# EIB-128.net
KiCad netlist of a schematic drawn in EAGLE
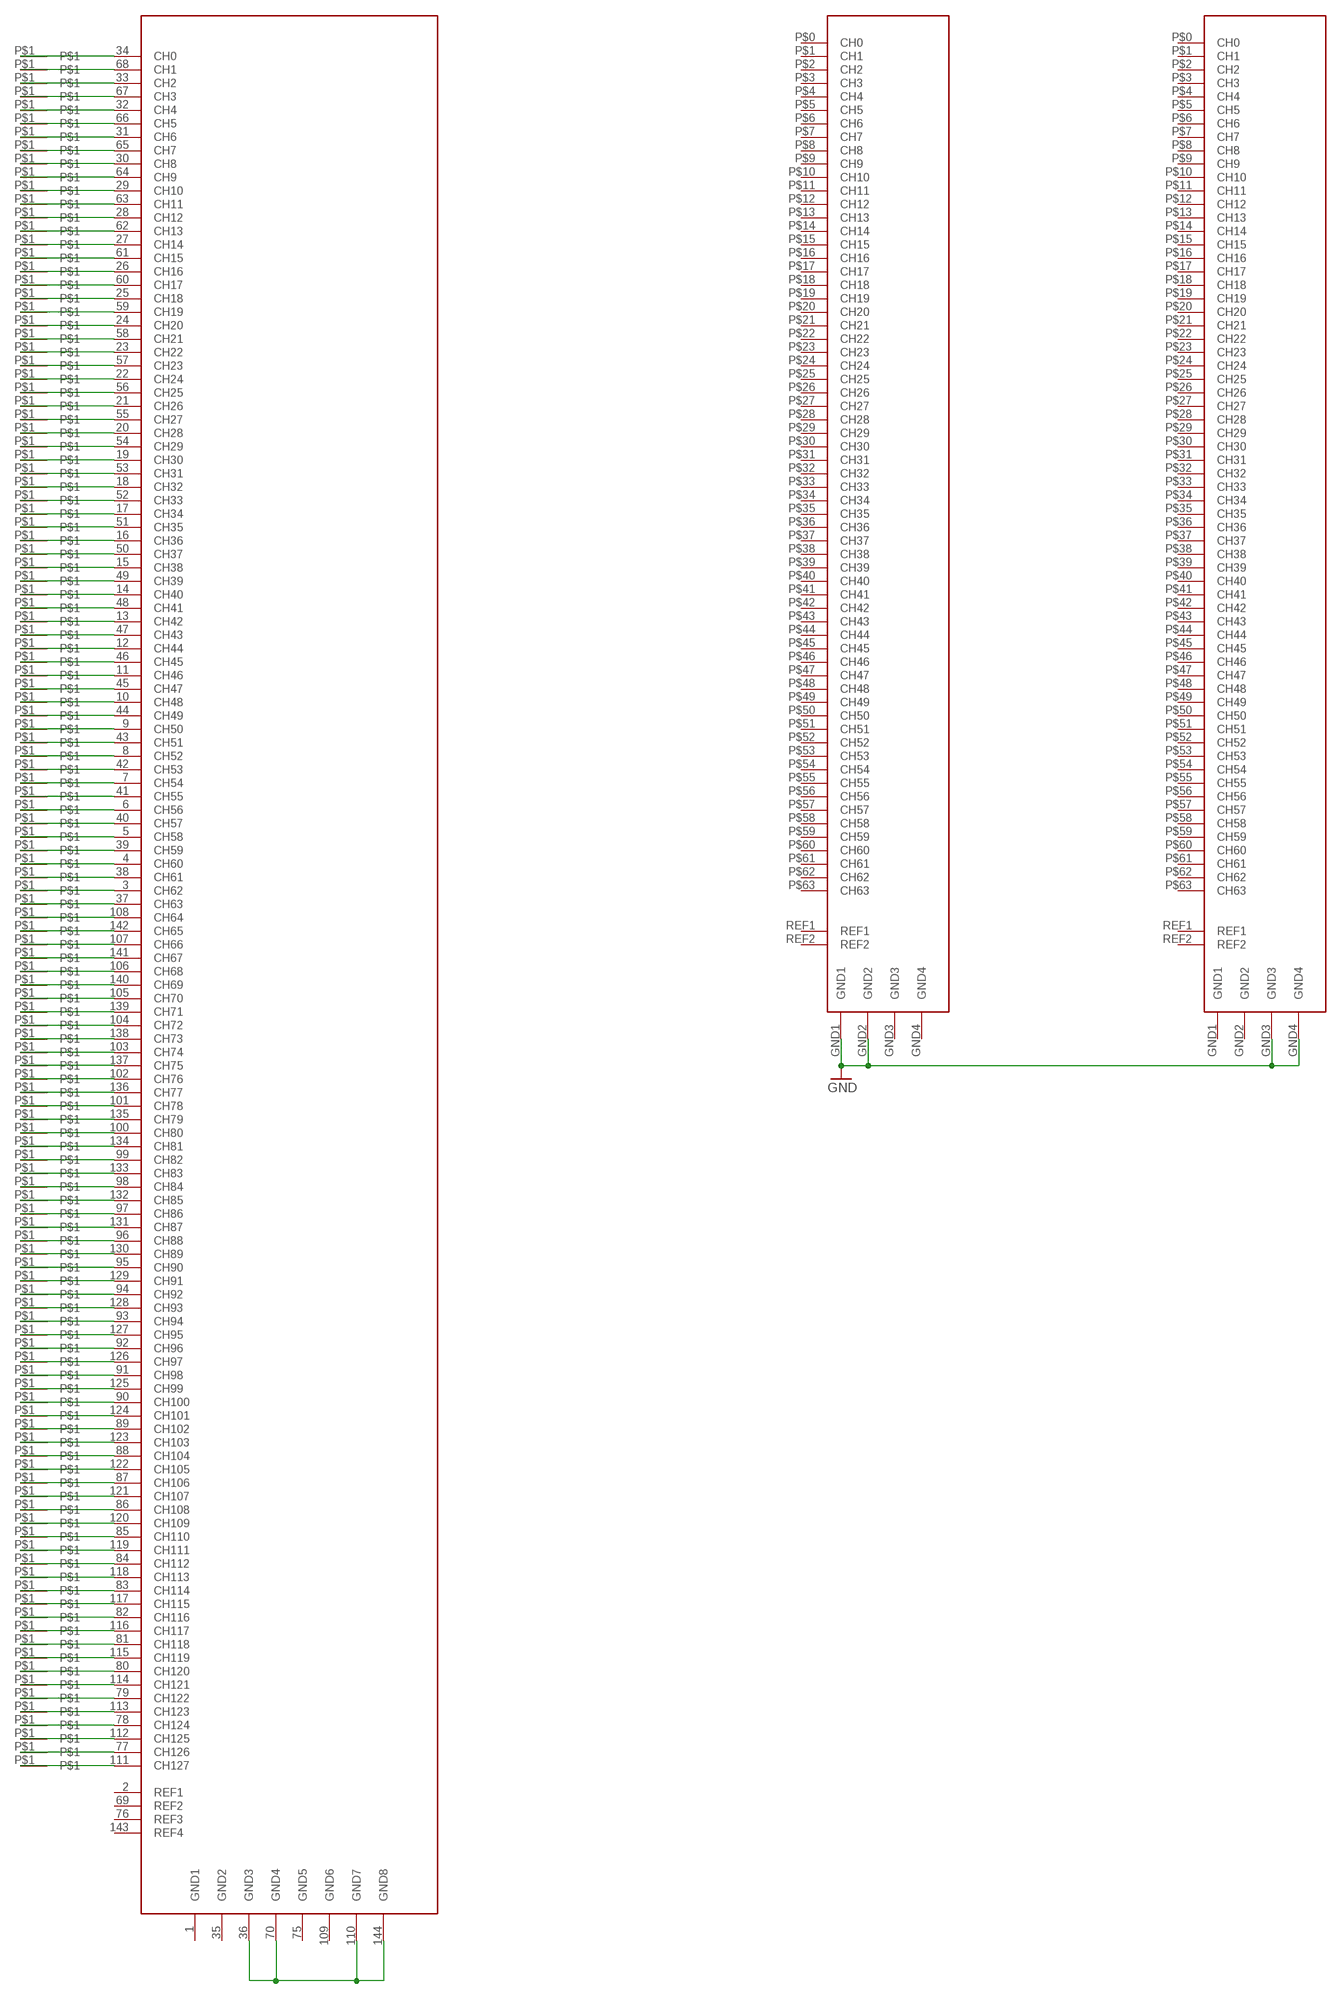
[diagram p0: schematic, sheet 1]

(export (version "E")
  (design (tool "Eeschema 10.0.6"))
  (components
    (comp (ref "H$0")
      (value "TARRAYSHUTTLEHOLE")
      (footprint "eagle-import:TARRAYSHUTTLEHOLE")
      (libsource (lib "eagle-import") (part "TARRAYSHUTTLEHOLE"))
    )
    (comp (ref "H$1")
      (value "TARRAYSHUTTLEHOLE")
      (footprint "eagle-import:TARRAYSHUTTLEHOLE")
      (libsource (lib "eagle-import") (part "TARRAYSHUTTLEHOLE"))
    )
    (comp (ref "H$2")
      (value "TARRAYSHUTTLEHOLE")
      (footprint "eagle-import:TARRAYSHUTTLEHOLE")
      (libsource (lib "eagle-import") (part "TARRAYSHUTTLEHOLE"))
    )
    (comp (ref "H$3")
      (value "TARRAYSHUTTLEHOLE")
      (footprint "eagle-import:TARRAYSHUTTLEHOLE")
      (libsource (lib "eagle-import") (part "TARRAYSHUTTLEHOLE"))
    )
    (comp (ref "H$4")
      (value "TARRAYSHUTTLEHOLE")
      (footprint "eagle-import:TARRAYSHUTTLEHOLE")
      (libsource (lib "eagle-import") (part "TARRAYSHUTTLEHOLE"))
    )
    (comp (ref "H$5")
      (value "TARRAYSHUTTLEHOLE")
      (footprint "eagle-import:TARRAYSHUTTLEHOLE")
      (libsource (lib "eagle-import") (part "TARRAYSHUTTLEHOLE"))
    )
    (comp (ref "H$6")
      (value "TARRAYSHUTTLEHOLE")
      (footprint "eagle-import:TARRAYSHUTTLEHOLE")
      (libsource (lib "eagle-import") (part "TARRAYSHUTTLEHOLE"))
    )
    (comp (ref "H$7")
      (value "TARRAYSHUTTLEHOLE")
      (footprint "eagle-import:TARRAYSHUTTLEHOLE")
      (libsource (lib "eagle-import") (part "TARRAYSHUTTLEHOLE"))
    )
    (comp (ref "H$8")
      (value "TARRAYSHUTTLEHOLE")
      (footprint "eagle-import:TARRAYSHUTTLEHOLE")
      (libsource (lib "eagle-import") (part "TARRAYSHUTTLEHOLE"))
    )
    (comp (ref "H$9")
      (value "TARRAYSHUTTLEHOLE")
      (footprint "eagle-import:TARRAYSHUTTLEHOLE")
      (libsource (lib "eagle-import") (part "TARRAYSHUTTLEHOLE"))
    )
    (comp (ref "H$10")
      (value "TARRAYSHUTTLEHOLE")
      (footprint "eagle-import:TARRAYSHUTTLEHOLE")
      (libsource (lib "eagle-import") (part "TARRAYSHUTTLEHOLE"))
    )
    (comp (ref "H$11")
      (value "TARRAYSHUTTLEHOLE")
      (footprint "eagle-import:TARRAYSHUTTLEHOLE")
      (libsource (lib "eagle-import") (part "TARRAYSHUTTLEHOLE"))
    )
    (comp (ref "H$12")
      (value "TARRAYSHUTTLEHOLE")
      (footprint "eagle-import:TARRAYSHUTTLEHOLE")
      (libsource (lib "eagle-import") (part "TARRAYSHUTTLEHOLE"))
    )
    (comp (ref "H$13")
      (value "TARRAYSHUTTLEHOLE")
      (footprint "eagle-import:TARRAYSHUTTLEHOLE")
      (libsource (lib "eagle-import") (part "TARRAYSHUTTLEHOLE"))
    )
    (comp (ref "H$14")
      (value "TARRAYSHUTTLEHOLE")
      (footprint "eagle-import:TARRAYSHUTTLEHOLE")
      (libsource (lib "eagle-import") (part "TARRAYSHUTTLEHOLE"))
    )
    (comp (ref "H$15")
      (value "TARRAYSHUTTLEHOLE")
      (footprint "eagle-import:TARRAYSHUTTLEHOLE")
      (libsource (lib "eagle-import") (part "TARRAYSHUTTLEHOLE"))
    )
    (comp (ref "H$16")
      (value "TARRAYSHUTTLEHOLE")
      (footprint "eagle-import:TARRAYSHUTTLEHOLE")
      (libsource (lib "eagle-import") (part "TARRAYSHUTTLEHOLE"))
    )
    (comp (ref "H$17")
      (value "TARRAYSHUTTLEHOLE")
      (footprint "eagle-import:TARRAYSHUTTLEHOLE")
      (libsource (lib "eagle-import") (part "TARRAYSHUTTLEHOLE"))
    )
    (comp (ref "H$18")
      (value "TARRAYSHUTTLEHOLE")
      (footprint "eagle-import:TARRAYSHUTTLEHOLE")
      (libsource (lib "eagle-import") (part "TARRAYSHUTTLEHOLE"))
    )
    (comp (ref "H$19")
      (value "TARRAYSHUTTLEHOLE")
      (footprint "eagle-import:TARRAYSHUTTLEHOLE")
      (libsource (lib "eagle-import") (part "TARRAYSHUTTLEHOLE"))
    )
    (comp (ref "H$20")
      (value "TARRAYSHUTTLEHOLE")
      (footprint "eagle-import:TARRAYSHUTTLEHOLE")
      (libsource (lib "eagle-import") (part "TARRAYSHUTTLEHOLE"))
    )
    (comp (ref "H$21")
      (value "TARRAYSHUTTLEHOLE")
      (footprint "eagle-import:TARRAYSHUTTLEHOLE")
      (libsource (lib "eagle-import") (part "TARRAYSHUTTLEHOLE"))
    )
    (comp (ref "H$22")
      (value "TARRAYSHUTTLEHOLE")
      (footprint "eagle-import:TARRAYSHUTTLEHOLE")
      (libsource (lib "eagle-import") (part "TARRAYSHUTTLEHOLE"))
    )
    (comp (ref "H$23")
      (value "TARRAYSHUTTLEHOLE")
      (footprint "eagle-import:TARRAYSHUTTLEHOLE")
      (libsource (lib "eagle-import") (part "TARRAYSHUTTLEHOLE"))
    )
    (comp (ref "H$24")
      (value "TARRAYSHUTTLEHOLE")
      (footprint "eagle-import:TARRAYSHUTTLEHOLE")
      (libsource (lib "eagle-import") (part "TARRAYSHUTTLEHOLE"))
    )
    (comp (ref "H$25")
      (value "TARRAYSHUTTLEHOLE")
      (footprint "eagle-import:TARRAYSHUTTLEHOLE")
      (libsource (lib "eagle-import") (part "TARRAYSHUTTLEHOLE"))
    )
    (comp (ref "H$26")
      (value "TARRAYSHUTTLEHOLE")
      (footprint "eagle-import:TARRAYSHUTTLEHOLE")
      (libsource (lib "eagle-import") (part "TARRAYSHUTTLEHOLE"))
    )
    (comp (ref "H$27")
      (value "TARRAYSHUTTLEHOLE")
      (footprint "eagle-import:TARRAYSHUTTLEHOLE")
      (libsource (lib "eagle-import") (part "TARRAYSHUTTLEHOLE"))
    )
    (comp (ref "H$28")
      (value "TARRAYSHUTTLEHOLE")
      (footprint "eagle-import:TARRAYSHUTTLEHOLE")
      (libsource (lib "eagle-import") (part "TARRAYSHUTTLEHOLE"))
    )
    (comp (ref "H$29")
      (value "TARRAYSHUTTLEHOLE")
      (footprint "eagle-import:TARRAYSHUTTLEHOLE")
      (libsource (lib "eagle-import") (part "TARRAYSHUTTLEHOLE"))
    )
    (comp (ref "H$30")
      (value "TARRAYSHUTTLEHOLE")
      (footprint "eagle-import:TARRAYSHUTTLEHOLE")
      (libsource (lib "eagle-import") (part "TARRAYSHUTTLEHOLE"))
    )
    (comp (ref "H$31")
      (value "TARRAYSHUTTLEHOLE")
      (footprint "eagle-import:TARRAYSHUTTLEHOLE")
      (libsource (lib "eagle-import") (part "TARRAYSHUTTLEHOLE"))
    )
    (comp (ref "H$32")
      (value "TARRAYSHUTTLEHOLE")
      (footprint "eagle-import:TARRAYSHUTTLEHOLE")
      (libsource (lib "eagle-import") (part "TARRAYSHUTTLEHOLE"))
    )
    (comp (ref "H$33")
      (value "TARRAYSHUTTLEHOLE")
      (footprint "eagle-import:TARRAYSHUTTLEHOLE")
      (libsource (lib "eagle-import") (part "TARRAYSHUTTLEHOLE"))
    )
    (comp (ref "H$34")
      (value "TARRAYSHUTTLEHOLE")
      (footprint "eagle-import:TARRAYSHUTTLEHOLE")
      (libsource (lib "eagle-import") (part "TARRAYSHUTTLEHOLE"))
    )
    (comp (ref "H$35")
      (value "TARRAYSHUTTLEHOLE")
      (footprint "eagle-import:TARRAYSHUTTLEHOLE")
      (libsource (lib "eagle-import") (part "TARRAYSHUTTLEHOLE"))
    )
    (comp (ref "H$36")
      (value "TARRAYSHUTTLEHOLE")
      (footprint "eagle-import:TARRAYSHUTTLEHOLE")
      (libsource (lib "eagle-import") (part "TARRAYSHUTTLEHOLE"))
    )
    (comp (ref "H$37")
      (value "TARRAYSHUTTLEHOLE")
      (footprint "eagle-import:TARRAYSHUTTLEHOLE")
      (libsource (lib "eagle-import") (part "TARRAYSHUTTLEHOLE"))
    )
    (comp (ref "H$38")
      (value "TARRAYSHUTTLEHOLE")
      (footprint "eagle-import:TARRAYSHUTTLEHOLE")
      (libsource (lib "eagle-import") (part "TARRAYSHUTTLEHOLE"))
    )
    (comp (ref "H$39")
      (value "TARRAYSHUTTLEHOLE")
      (footprint "eagle-import:TARRAYSHUTTLEHOLE")
      (libsource (lib "eagle-import") (part "TARRAYSHUTTLEHOLE"))
    )
    (comp (ref "H$40")
      (value "TARRAYSHUTTLEHOLE")
      (footprint "eagle-import:TARRAYSHUTTLEHOLE")
      (libsource (lib "eagle-import") (part "TARRAYSHUTTLEHOLE"))
    )
    (comp (ref "H$41")
      (value "TARRAYSHUTTLEHOLE")
      (footprint "eagle-import:TARRAYSHUTTLEHOLE")
      (libsource (lib "eagle-import") (part "TARRAYSHUTTLEHOLE"))
    )
    (comp (ref "H$42")
      (value "TARRAYSHUTTLEHOLE")
      (footprint "eagle-import:TARRAYSHUTTLEHOLE")
      (libsource (lib "eagle-import") (part "TARRAYSHUTTLEHOLE"))
    )
    (comp (ref "H$43")
      (value "TARRAYSHUTTLEHOLE")
      (footprint "eagle-import:TARRAYSHUTTLEHOLE")
      (libsource (lib "eagle-import") (part "TARRAYSHUTTLEHOLE"))
    )
    (comp (ref "H$44")
      (value "TARRAYSHUTTLEHOLE")
      (footprint "eagle-import:TARRAYSHUTTLEHOLE")
      (libsource (lib "eagle-import") (part "TARRAYSHUTTLEHOLE"))
    )
    (comp (ref "H$45")
      (value "TARRAYSHUTTLEHOLE")
      (footprint "eagle-import:TARRAYSHUTTLEHOLE")
      (libsource (lib "eagle-import") (part "TARRAYSHUTTLEHOLE"))
    )
    (comp (ref "H$46")
      (value "TARRAYSHUTTLEHOLE")
      (footprint "eagle-import:TARRAYSHUTTLEHOLE")
      (libsource (lib "eagle-import") (part "TARRAYSHUTTLEHOLE"))
    )
    (comp (ref "H$47")
      (value "TARRAYSHUTTLEHOLE")
      (footprint "eagle-import:TARRAYSHUTTLEHOLE")
      (libsource (lib "eagle-import") (part "TARRAYSHUTTLEHOLE"))
    )
    (comp (ref "H$48")
      (value "TARRAYSHUTTLEHOLE")
      (footprint "eagle-import:TARRAYSHUTTLEHOLE")
      (libsource (lib "eagle-import") (part "TARRAYSHUTTLEHOLE"))
    )
    (comp (ref "H$49")
      (value "TARRAYSHUTTLEHOLE")
      (footprint "eagle-import:TARRAYSHUTTLEHOLE")
      (libsource (lib "eagle-import") (part "TARRAYSHUTTLEHOLE"))
    )
    (comp (ref "H$50")
      (value "TARRAYSHUTTLEHOLE")
      (footprint "eagle-import:TARRAYSHUTTLEHOLE")
      (libsource (lib "eagle-import") (part "TARRAYSHUTTLEHOLE"))
    )
    (comp (ref "H$51")
      (value "TARRAYSHUTTLEHOLE")
      (footprint "eagle-import:TARRAYSHUTTLEHOLE")
      (libsource (lib "eagle-import") (part "TARRAYSHUTTLEHOLE"))
    )
    (comp (ref "H$52")
      (value "TARRAYSHUTTLEHOLE")
      (footprint "eagle-import:TARRAYSHUTTLEHOLE")
      (libsource (lib "eagle-import") (part "TARRAYSHUTTLEHOLE"))
    )
    (comp (ref "H$53")
      (value "TARRAYSHUTTLEHOLE")
      (footprint "eagle-import:TARRAYSHUTTLEHOLE")
      (libsource (lib "eagle-import") (part "TARRAYSHUTTLEHOLE"))
    )
    (comp (ref "H$54")
      (value "TARRAYSHUTTLEHOLE")
      (footprint "eagle-import:TARRAYSHUTTLEHOLE")
      (libsource (lib "eagle-import") (part "TARRAYSHUTTLEHOLE"))
    )
    (comp (ref "H$55")
      (value "TARRAYSHUTTLEHOLE")
      (footprint "eagle-import:TARRAYSHUTTLEHOLE")
      (libsource (lib "eagle-import") (part "TARRAYSHUTTLEHOLE"))
    )
    (comp (ref "H$56")
      (value "TARRAYSHUTTLEHOLE")
      (footprint "eagle-import:TARRAYSHUTTLEHOLE")
      (libsource (lib "eagle-import") (part "TARRAYSHUTTLEHOLE"))
    )
    (comp (ref "H$57")
      (value "TARRAYSHUTTLEHOLE")
      (footprint "eagle-import:TARRAYSHUTTLEHOLE")
      (libsource (lib "eagle-import") (part "TARRAYSHUTTLEHOLE"))
    )
    (comp (ref "H$58")
      (value "TARRAYSHUTTLEHOLE")
      (footprint "eagle-import:TARRAYSHUTTLEHOLE")
      (libsource (lib "eagle-import") (part "TARRAYSHUTTLEHOLE"))
    )
    (comp (ref "H$59")
      (value "TARRAYSHUTTLEHOLE")
      (footprint "eagle-import:TARRAYSHUTTLEHOLE")
      (libsource (lib "eagle-import") (part "TARRAYSHUTTLEHOLE"))
    )
    (comp (ref "H$60")
      (value "TARRAYSHUTTLEHOLE")
      (footprint "eagle-import:TARRAYSHUTTLEHOLE")
      (libsource (lib "eagle-import") (part "TARRAYSHUTTLEHOLE"))
    )
    (comp (ref "H$61")
      (value "TARRAYSHUTTLEHOLE")
      (footprint "eagle-import:TARRAYSHUTTLEHOLE")
      (libsource (lib "eagle-import") (part "TARRAYSHUTTLEHOLE"))
    )
    (comp (ref "H$62")
      (value "TARRAYSHUTTLEHOLE")
      (footprint "eagle-import:TARRAYSHUTTLEHOLE")
      (libsource (lib "eagle-import") (part "TARRAYSHUTTLEHOLE"))
    )
    (comp (ref "H$63")
      (value "TARRAYSHUTTLEHOLE")
      (footprint "eagle-import:TARRAYSHUTTLEHOLE")
      (libsource (lib "eagle-import") (part "TARRAYSHUTTLEHOLE"))
    )
    (comp (ref "H$64")
      (value "TARRAYSHUTTLEHOLE")
      (footprint "eagle-import:TARRAYSHUTTLEHOLE")
      (libsource (lib "eagle-import") (part "TARRAYSHUTTLEHOLE"))
    )
    (comp (ref "H$65")
      (value "TARRAYSHUTTLEHOLE")
      (footprint "eagle-import:TARRAYSHUTTLEHOLE")
      (libsource (lib "eagle-import") (part "TARRAYSHUTTLEHOLE"))
    )
    (comp (ref "H$66")
      (value "TARRAYSHUTTLEHOLE")
      (footprint "eagle-import:TARRAYSHUTTLEHOLE")
      (libsource (lib "eagle-import") (part "TARRAYSHUTTLEHOLE"))
    )
    (comp (ref "H$67")
      (value "TARRAYSHUTTLEHOLE")
      (footprint "eagle-import:TARRAYSHUTTLEHOLE")
      (libsource (lib "eagle-import") (part "TARRAYSHUTTLEHOLE"))
    )
    (comp (ref "H$68")
      (value "TARRAYSHUTTLEHOLE")
      (footprint "eagle-import:TARRAYSHUTTLEHOLE")
      (libsource (lib "eagle-import") (part "TARRAYSHUTTLEHOLE"))
    )
    (comp (ref "H$69")
      (value "TARRAYSHUTTLEHOLE")
      (footprint "eagle-import:TARRAYSHUTTLEHOLE")
      (libsource (lib "eagle-import") (part "TARRAYSHUTTLEHOLE"))
    )
    (comp (ref "H$70")
      (value "TARRAYSHUTTLEHOLE")
      (footprint "eagle-import:TARRAYSHUTTLEHOLE")
      (libsource (lib "eagle-import") (part "TARRAYSHUTTLEHOLE"))
    )
    (comp (ref "H$71")
      (value "TARRAYSHUTTLEHOLE")
      (footprint "eagle-import:TARRAYSHUTTLEHOLE")
      (libsource (lib "eagle-import") (part "TARRAYSHUTTLEHOLE"))
    )
    (comp (ref "H$72")
      (value "TARRAYSHUTTLEHOLE")
      (footprint "eagle-import:TARRAYSHUTTLEHOLE")
      (libsource (lib "eagle-import") (part "TARRAYSHUTTLEHOLE"))
    )
    (comp (ref "H$73")
      (value "TARRAYSHUTTLEHOLE")
      (footprint "eagle-import:TARRAYSHUTTLEHOLE")
      (libsource (lib "eagle-import") (part "TARRAYSHUTTLEHOLE"))
    )
    (comp (ref "H$74")
      (value "TARRAYSHUTTLEHOLE")
      (footprint "eagle-import:TARRAYSHUTTLEHOLE")
      (libsource (lib "eagle-import") (part "TARRAYSHUTTLEHOLE"))
    )
    (comp (ref "H$75")
      (value "TARRAYSHUTTLEHOLE")
      (footprint "eagle-import:TARRAYSHUTTLEHOLE")
      (libsource (lib "eagle-import") (part "TARRAYSHUTTLEHOLE"))
    )
    (comp (ref "H$76")
      (value "TARRAYSHUTTLEHOLE")
      (footprint "eagle-import:TARRAYSHUTTLEHOLE")
      (libsource (lib "eagle-import") (part "TARRAYSHUTTLEHOLE"))
    )
    (comp (ref "H$77")
      (value "TARRAYSHUTTLEHOLE")
      (footprint "eagle-import:TARRAYSHUTTLEHOLE")
      (libsource (lib "eagle-import") (part "TARRAYSHUTTLEHOLE"))
    )
    (comp (ref "H$78")
      (value "TARRAYSHUTTLEHOLE")
      (footprint "eagle-import:TARRAYSHUTTLEHOLE")
      (libsource (lib "eagle-import") (part "TARRAYSHUTTLEHOLE"))
    )
    (comp (ref "H$79")
      (value "TARRAYSHUTTLEHOLE")
      (footprint "eagle-import:TARRAYSHUTTLEHOLE")
      (libsource (lib "eagle-import") (part "TARRAYSHUTTLEHOLE"))
    )
    (comp (ref "H$80")
      (value "TARRAYSHUTTLEHOLE")
      (footprint "eagle-import:TARRAYSHUTTLEHOLE")
      (libsource (lib "eagle-import") (part "TARRAYSHUTTLEHOLE"))
    )
    (comp (ref "H$81")
      (value "TARRAYSHUTTLEHOLE")
      (footprint "eagle-import:TARRAYSHUTTLEHOLE")
      (libsource (lib "eagle-import") (part "TARRAYSHUTTLEHOLE"))
    )
    (comp (ref "H$82")
      (value "TARRAYSHUTTLEHOLE")
      (footprint "eagle-import:TARRAYSHUTTLEHOLE")
      (libsource (lib "eagle-import") (part "TARRAYSHUTTLEHOLE"))
    )
    (comp (ref "H$83")
      (value "TARRAYSHUTTLEHOLE")
      (footprint "eagle-import:TARRAYSHUTTLEHOLE")
      (libsource (lib "eagle-import") (part "TARRAYSHUTTLEHOLE"))
    )
    (comp (ref "H$84")
      (value "TARRAYSHUTTLEHOLE")
      (footprint "eagle-import:TARRAYSHUTTLEHOLE")
      (libsource (lib "eagle-import") (part "TARRAYSHUTTLEHOLE"))
    )
    (comp (ref "H$85")
      (value "TARRAYSHUTTLEHOLE")
      (footprint "eagle-import:TARRAYSHUTTLEHOLE")
      (libsource (lib "eagle-import") (part "TARRAYSHUTTLEHOLE"))
    )
    (comp (ref "H$86")
      (value "TARRAYSHUTTLEHOLE")
      (footprint "eagle-import:TARRAYSHUTTLEHOLE")
      (libsource (lib "eagle-import") (part "TARRAYSHUTTLEHOLE"))
    )
    (comp (ref "H$87")
      (value "TARRAYSHUTTLEHOLE")
      (footprint "eagle-import:TARRAYSHUTTLEHOLE")
      (libsource (lib "eagle-import") (part "TARRAYSHUTTLEHOLE"))
    )
    (comp (ref "H$88")
      (value "TARRAYSHUTTLEHOLE")
      (footprint "eagle-import:TARRAYSHUTTLEHOLE")
      (libsource (lib "eagle-import") (part "TARRAYSHUTTLEHOLE"))
    )
    (comp (ref "H$89")
      (value "TARRAYSHUTTLEHOLE")
      (footprint "eagle-import:TARRAYSHUTTLEHOLE")
      (libsource (lib "eagle-import") (part "TARRAYSHUTTLEHOLE"))
    )
    (comp (ref "H$90")
      (value "TARRAYSHUTTLEHOLE")
      (footprint "eagle-import:TARRAYSHUTTLEHOLE")
      (libsource (lib "eagle-import") (part "TARRAYSHUTTLEHOLE"))
    )
    (comp (ref "H$91")
      (value "TARRAYSHUTTLEHOLE")
      (footprint "eagle-import:TARRAYSHUTTLEHOLE")
      (libsource (lib "eagle-import") (part "TARRAYSHUTTLEHOLE"))
    )
    (comp (ref "H$92")
      (value "TARRAYSHUTTLEHOLE")
      (footprint "eagle-import:TARRAYSHUTTLEHOLE")
      (libsource (lib "eagle-import") (part "TARRAYSHUTTLEHOLE"))
    )
    (comp (ref "H$93")
      (value "TARRAYSHUTTLEHOLE")
      (footprint "eagle-import:TARRAYSHUTTLEHOLE")
      (libsource (lib "eagle-import") (part "TARRAYSHUTTLEHOLE"))
    )
    (comp (ref "H$94")
      (value "TARRAYSHUTTLEHOLE")
      (footprint "eagle-import:TARRAYSHUTTLEHOLE")
      (libsource (lib "eagle-import") (part "TARRAYSHUTTLEHOLE"))
    )
    (comp (ref "H$95")
      (value "TARRAYSHUTTLEHOLE")
      (footprint "eagle-import:TARRAYSHUTTLEHOLE")
      (libsource (lib "eagle-import") (part "TARRAYSHUTTLEHOLE"))
    )
    (comp (ref "H$96")
      (value "TARRAYSHUTTLEHOLE")
      (footprint "eagle-import:TARRAYSHUTTLEHOLE")
      (libsource (lib "eagle-import") (part "TARRAYSHUTTLEHOLE"))
    )
    (comp (ref "H$97")
      (value "TARRAYSHUTTLEHOLE")
      (footprint "eagle-import:TARRAYSHUTTLEHOLE")
      (libsource (lib "eagle-import") (part "TARRAYSHUTTLEHOLE"))
    )
    (comp (ref "H$98")
      (value "TARRAYSHUTTLEHOLE")
      (footprint "eagle-import:TARRAYSHUTTLEHOLE")
      (libsource (lib "eagle-import") (part "TARRAYSHUTTLEHOLE"))
    )
    (comp (ref "H$99")
      (value "TARRAYSHUTTLEHOLE")
      (footprint "eagle-import:TARRAYSHUTTLEHOLE")
      (libsource (lib "eagle-import") (part "TARRAYSHUTTLEHOLE"))
    )
    (comp (ref "H$100")
      (value "TARRAYSHUTTLEHOLE")
      (footprint "eagle-import:TARRAYSHUTTLEHOLE")
      (libsource (lib "eagle-import") (part "TARRAYSHUTTLEHOLE"))
    )
    (comp (ref "H$101")
      (value "TARRAYSHUTTLEHOLE")
      (footprint "eagle-import:TARRAYSHUTTLEHOLE")
      (libsource (lib "eagle-import") (part "TARRAYSHUTTLEHOLE"))
    )
    (comp (ref "H$102")
      (value "TARRAYSHUTTLEHOLE")
      (footprint "eagle-import:TARRAYSHUTTLEHOLE")
      (libsource (lib "eagle-import") (part "TARRAYSHUTTLEHOLE"))
    )
    (comp (ref "H$103")
      (value "TARRAYSHUTTLEHOLE")
      (footprint "eagle-import:TARRAYSHUTTLEHOLE")
      (libsource (lib "eagle-import") (part "TARRAYSHUTTLEHOLE"))
    )
    (comp (ref "H$104")
      (value "TARRAYSHUTTLEHOLE")
      (footprint "eagle-import:TARRAYSHUTTLEHOLE")
      (libsource (lib "eagle-import") (part "TARRAYSHUTTLEHOLE"))
    )
    (comp (ref "H$105")
      (value "TARRAYSHUTTLEHOLE")
      (footprint "eagle-import:TARRAYSHUTTLEHOLE")
      (libsource (lib "eagle-import") (part "TARRAYSHUTTLEHOLE"))
    )
    (comp (ref "H$106")
      (value "TARRAYSHUTTLEHOLE")
      (footprint "eagle-import:TARRAYSHUTTLEHOLE")
      (libsource (lib "eagle-import") (part "TARRAYSHUTTLEHOLE"))
    )
    (comp (ref "H$107")
      (value "TARRAYSHUTTLEHOLE")
      (footprint "eagle-import:TARRAYSHUTTLEHOLE")
      (libsource (lib "eagle-import") (part "TARRAYSHUTTLEHOLE"))
    )
    (comp (ref "H$108")
      (value "TARRAYSHUTTLEHOLE")
      (footprint "eagle-import:TARRAYSHUTTLEHOLE")
      (libsource (lib "eagle-import") (part "TARRAYSHUTTLEHOLE"))
    )
    (comp (ref "H$109")
      (value "TARRAYSHUTTLEHOLE")
      (footprint "eagle-import:TARRAYSHUTTLEHOLE")
      (libsource (lib "eagle-import") (part "TARRAYSHUTTLEHOLE"))
    )
    (comp (ref "H$110")
      (value "TARRAYSHUTTLEHOLE")
      (footprint "eagle-import:TARRAYSHUTTLEHOLE")
      (libsource (lib "eagle-import") (part "TARRAYSHUTTLEHOLE"))
    )
    (comp (ref "H$111")
      (value "TARRAYSHUTTLEHOLE")
      (footprint "eagle-import:TARRAYSHUTTLEHOLE")
      (libsource (lib "eagle-import") (part "TARRAYSHUTTLEHOLE"))
    )
    (comp (ref "H$112")
      (value "TARRAYSHUTTLEHOLE")
      (footprint "eagle-import:TARRAYSHUTTLEHOLE")
      (libsource (lib "eagle-import") (part "TARRAYSHUTTLEHOLE"))
    )
    (comp (ref "H$113")
      (value "TARRAYSHUTTLEHOLE")
      (footprint "eagle-import:TARRAYSHUTTLEHOLE")
      (libsource (lib "eagle-import") (part "TARRAYSHUTTLEHOLE"))
    )
    (comp (ref "H$114")
      (value "TARRAYSHUTTLEHOLE")
      (footprint "eagle-import:TARRAYSHUTTLEHOLE")
      (libsource (lib "eagle-import") (part "TARRAYSHUTTLEHOLE"))
    )
    (comp (ref "H$115")
      (value "TARRAYSHUTTLEHOLE")
      (footprint "eagle-import:TARRAYSHUTTLEHOLE")
      (libsource (lib "eagle-import") (part "TARRAYSHUTTLEHOLE"))
    )
    (comp (ref "H$116")
      (value "TARRAYSHUTTLEHOLE")
      (footprint "eagle-import:TARRAYSHUTTLEHOLE")
      (libsource (lib "eagle-import") (part "TARRAYSHUTTLEHOLE"))
    )
    (comp (ref "H$117")
      (value "TARRAYSHUTTLEHOLE")
      (footprint "eagle-import:TARRAYSHUTTLEHOLE")
      (libsource (lib "eagle-import") (part "TARRAYSHUTTLEHOLE"))
    )
    (comp (ref "H$118")
      (value "TARRAYSHUTTLEHOLE")
      (footprint "eagle-import:TARRAYSHUTTLEHOLE")
      (libsource (lib "eagle-import") (part "TARRAYSHUTTLEHOLE"))
    )
    (comp (ref "H$119")
      (value "TARRAYSHUTTLEHOLE")
      (footprint "eagle-import:TARRAYSHUTTLEHOLE")
      (libsource (lib "eagle-import") (part "TARRAYSHUTTLEHOLE"))
    )
    (comp (ref "H$120")
      (value "TARRAYSHUTTLEHOLE")
      (footprint "eagle-import:TARRAYSHUTTLEHOLE")
      (libsource (lib "eagle-import") (part "TARRAYSHUTTLEHOLE"))
    )
    (comp (ref "H$121")
      (value "TARRAYSHUTTLEHOLE")
      (footprint "eagle-import:TARRAYSHUTTLEHOLE")
      (libsource (lib "eagle-import") (part "TARRAYSHUTTLEHOLE"))
    )
    (comp (ref "H$122")
      (value "TARRAYSHUTTLEHOLE")
      (footprint "eagle-import:TARRAYSHUTTLEHOLE")
      (libsource (lib "eagle-import") (part "TARRAYSHUTTLEHOLE"))
    )
    (comp (ref "H$123")
      (value "TARRAYSHUTTLEHOLE")
      (footprint "eagle-import:TARRAYSHUTTLEHOLE")
      (libsource (lib "eagle-import") (part "TARRAYSHUTTLEHOLE"))
    )
    (comp (ref "H$124")
      (value "TARRAYSHUTTLEHOLE")
      (footprint "eagle-import:TARRAYSHUTTLEHOLE")
      (libsource (lib "eagle-import") (part "TARRAYSHUTTLEHOLE"))
    )
    (comp (ref "H$125")
      (value "TARRAYSHUTTLEHOLE")
      (footprint "eagle-import:TARRAYSHUTTLEHOLE")
      (libsource (lib "eagle-import") (part "TARRAYSHUTTLEHOLE"))
    )
    (comp (ref "H$126")
      (value "TARRAYSHUTTLEHOLE")
      (footprint "eagle-import:TARRAYSHUTTLEHOLE")
      (libsource (lib "eagle-import") (part "TARRAYSHUTTLEHOLE"))
    )
    (comp (ref "H$127")
      (value "TARRAYSHUTTLEHOLE")
      (footprint "eagle-import:TARRAYSHUTTLEHOLE")
      (libsource (lib "eagle-import") (part "TARRAYSHUTTLEHOLE"))
    )
    (comp (ref "U$1")
      (value "DF40C-70DP")
      (footprint "eagle-import:DF40C-70DP")
      (libsource (lib "eagle-import") (part "DF40C-70DP"))
    )
    (comp (ref "U$2")
      (value "DF40C-70DP")
      (footprint "eagle-import:DF40C-70DP")
      (libsource (lib "eagle-import") (part "DF40C-70DP"))
    )
    (comp (ref "U$3")
      (value "128CH-MODULE")
      (footprint "eagle-import:128CH-MODULE")
      (libsource (lib "eagle-import") (part "128CH-MODULE"))
    )
  )
  (nets
    (net (code "1") (name "/GND1") (class "Default")
      (node (ref "U$3") (pin "1") (pinfunction "GND1_1") (pintype "power_in"))
    )
    (net (code "2") (name "/GND2") (class "Default")
      (node (ref "U$3") (pin "35") (pinfunction "GND2_35") (pintype "power_in"))
    )
    (net (code "3") (name "/GND5") (class "Default")
      (node (ref "U$3") (pin "75") (pinfunction "GND5_75") (pintype "power_in"))
    )
    (net (code "4") (name "/GND6") (class "Default")
      (node (ref "U$3") (pin "109") (pinfunction "GND6_109") (pintype "power_in"))
    )
    (net (code "5") (name "GND") (class "Default")
      (node (ref "U$1") (pin "GND1") (pinfunction "GND1_GND1") (pintype "bidirectional"))
      (node (ref "U$1") (pin "GND2") (pinfunction "GND2_GND2") (pintype "bidirectional"))
      (node (ref "U$2") (pin "GND3") (pinfunction "GND3_GND3") (pintype "bidirectional"))
      (node (ref "U$2") (pin "GND4") (pinfunction "GND4_GND4") (pintype "bidirectional"))
    )
    (net (code "6") (name "Net-(U$3-CH0)") (class "Default")
      (node (ref "H$0") (pin "P$1") (pinfunction "P$1_P$1") (pintype "bidirectional"))
      (node (ref "U$3") (pin "34") (pinfunction "CH0_34") (pintype "input"))
    )
    (net (code "7") (name "Net-(U$3-CH1)") (class "Default")
      (node (ref "H$1") (pin "P$1") (pinfunction "P$1_P$1") (pintype "bidirectional"))
      (node (ref "U$3") (pin "68") (pinfunction "CH1_68") (pintype "input"))
    )
    (net (code "8") (name "Net-(U$3-CH2)") (class "Default")
      (node (ref "H$2") (pin "P$1") (pinfunction "P$1_P$1") (pintype "bidirectional"))
      (node (ref "U$3") (pin "33") (pinfunction "CH2_33") (pintype "input"))
    )
    (net (code "9") (name "Net-(U$3-CH3)") (class "Default")
      (node (ref "H$3") (pin "P$1") (pinfunction "P$1_P$1") (pintype "bidirectional"))
      (node (ref "U$3") (pin "67") (pinfunction "CH3_67") (pintype "input"))
    )
    (net (code "10") (name "Net-(U$3-CH4)") (class "Default")
      (node (ref "H$4") (pin "P$1") (pinfunction "P$1_P$1") (pintype "bidirectional"))
      (node (ref "U$3") (pin "32") (pinfunction "CH4_32") (pintype "input"))
    )
    (net (code "11") (name "Net-(U$3-CH5)") (class "Default")
      (node (ref "H$5") (pin "P$1") (pinfunction "P$1_P$1") (pintype "bidirectional"))
      (node (ref "U$3") (pin "66") (pinfunction "CH5_66") (pintype "input"))
    )
    (net (code "12") (name "Net-(U$3-CH6)") (class "Default")
      (node (ref "H$6") (pin "P$1") (pinfunction "P$1_P$1") (pintype "bidirectional"))
      (node (ref "U$3") (pin "31") (pinfunction "CH6_31") (pintype "input"))
    )
    (net (code "13") (name "Net-(U$3-CH7)") (class "Default")
      (node (ref "H$7") (pin "P$1") (pinfunction "P$1_P$1") (pintype "bidirectional"))
      (node (ref "U$3") (pin "65") (pinfunction "CH7_65") (pintype "input"))
    )
    (net (code "14") (name "Net-(U$3-CH8)") (class "Default")
      (node (ref "H$8") (pin "P$1") (pinfunction "P$1_P$1") (pintype "bidirectional"))
      (node (ref "U$3") (pin "30") (pinfunction "CH8_30") (pintype "input"))
    )
    (net (code "15") (name "Net-(U$3-CH9)") (class "Default")
      (node (ref "H$9") (pin "P$1") (pinfunction "P$1_P$1") (pintype "bidirectional"))
      (node (ref "U$3") (pin "64") (pinfunction "CH9_64") (pintype "input"))
    )
    (net (code "16") (name "Net-(U$3-CH10)") (class "Default")
      (node (ref "H$10") (pin "P$1") (pinfunction "P$1_P$1") (pintype "bidirectional"))
      (node (ref "U$3") (pin "29") (pinfunction "CH10_29") (pintype "input"))
    )
    (net (code "17") (name "Net-(U$3-CH11)") (class "Default")
      (node (ref "H$11") (pin "P$1") (pinfunction "P$1_P$1") (pintype "bidirectional"))
      (node (ref "U$3") (pin "63") (pinfunction "CH11_63") (pintype "input"))
    )
    (net (code "18") (name "Net-(U$3-CH12)") (class "Default")
      (node (ref "H$12") (pin "P$1") (pinfunction "P$1_P$1") (pintype "bidirectional"))
      (node (ref "U$3") (pin "28") (pinfunction "CH12_28") (pintype "input"))
    )
    (net (code "19") (name "Net-(U$3-CH13)") (class "Default")
      (node (ref "H$13") (pin "P$1") (pinfunction "P$1_P$1") (pintype "bidirectional"))
      (node (ref "U$3") (pin "62") (pinfunction "CH13_62") (pintype "input"))
    )
    (net (code "20") (name "Net-(U$3-CH14)") (class "Default")
      (node (ref "H$14") (pin "P$1") (pinfunction "P$1_P$1") (pintype "bidirectional"))
      (node (ref "U$3") (pin "27") (pinfunction "CH14_27") (pintype "input"))
    )
    (net (code "21") (name "Net-(U$3-CH15)") (class "Default")
      (node (ref "H$15") (pin "P$1") (pinfunction "P$1_P$1") (pintype "bidirectional"))
      (node (ref "U$3") (pin "61") (pinfunction "CH15_61") (pintype "input"))
    )
    (net (code "22") (name "Net-(U$3-CH16)") (class "Default")
      (node (ref "H$16") (pin "P$1") (pinfunction "P$1_P$1") (pintype "bidirectional"))
      (node (ref "U$3") (pin "26") (pinfunction "CH16_26") (pintype "input"))
    )
    (net (code "23") (name "Net-(U$3-CH17)") (class "Default")
      (node (ref "H$17") (pin "P$1") (pinfunction "P$1_P$1") (pintype "bidirectional"))
      (node (ref "U$3") (pin "60") (pinfunction "CH17_60") (pintype "input"))
    )
    (net (code "24") (name "Net-(U$3-CH18)") (class "Default")
      (node (ref "H$18") (pin "P$1") (pinfunction "P$1_P$1") (pintype "bidirectional"))
      (node (ref "U$3") (pin "25") (pinfunction "CH18_25") (pintype "input"))
    )
    (net (code "25") (name "Net-(U$3-CH19)") (class "Default")
      (node (ref "H$19") (pin "P$1") (pinfunction "P$1_P$1") (pintype "bidirectional"))
      (node (ref "U$3") (pin "59") (pinfunction "CH19_59") (pintype "input"))
    )
    (net (code "26") (name "Net-(U$3-CH20)") (class "Default")
      (node (ref "H$20") (pin "P$1") (pinfunction "P$1_P$1") (pintype "bidirectional"))
      (node (ref "U$3") (pin "24") (pinfunction "CH20_24") (pintype "input"))
    )
    (net (code "27") (name "Net-(U$3-CH21)") (class "Default")
      (node (ref "H$21") (pin "P$1") (pinfunction "P$1_P$1") (pintype "bidirectional"))
      (node (ref "U$3") (pin "58") (pinfunction "CH21_58") (pintype "input"))
    )
    (net (code "28") (name "Net-(U$3-CH22)") (class "Default")
      (node (ref "H$22") (pin "P$1") (pinfunction "P$1_P$1") (pintype "bidirectional"))
      (node (ref "U$3") (pin "23") (pinfunction "CH22_23") (pintype "input"))
    )
    (net (code "29") (name "Net-(U$3-CH23)") (class "Default")
      (node (ref "H$23") (pin "P$1") (pinfunction "P$1_P$1") (pintype "bidirectional"))
      (node (ref "U$3") (pin "57") (pinfunction "CH23_57") (pintype "input"))
    )
    (net (code "30") (name "Net-(U$3-CH24)") (class "Default")
      (node (ref "H$24") (pin "P$1") (pinfunction "P$1_P$1") (pintype "bidirectional"))
      (node (ref "U$3") (pin "22") (pinfunction "CH24_22") (pintype "input"))
    )
    (net (code "31") (name "Net-(U$3-CH25)") (class "Default")
      (node (ref "H$25") (pin "P$1") (pinfunction "P$1_P$1") (pintype "bidirectional"))
      (node (ref "U$3") (pin "56") (pinfunction "CH25_56") (pintype "input"))
    )
    (net (code "32") (name "Net-(U$3-CH26)") (class "Default")
      (node (ref "H$26") (pin "P$1") (pinfunction "P$1_P$1") (pintype "bidirectional"))
      (node (ref "U$3") (pin "21") (pinfunction "CH26_21") (pintype "input"))
    )
    (net (code "33") (name "Net-(U$3-CH27)") (class "Default")
      (node (ref "H$27") (pin "P$1") (pinfunction "P$1_P$1") (pintype "bidirectional"))
      (node (ref "U$3") (pin "55") (pinfunction "CH27_55") (pintype "input"))
    )
    (net (code "34") (name "Net-(U$3-CH28)") (class "Default")
      (node (ref "H$28") (pin "P$1") (pinfunction "P$1_P$1") (pintype "bidirectional"))
      (node (ref "U$3") (pin "20") (pinfunction "CH28_20") (pintype "input"))
    )
    (net (code "35") (name "Net-(U$3-CH29)") (class "Default")
      (node (ref "H$29") (pin "P$1") (pinfunction "P$1_P$1") (pintype "bidirectional"))
      (node (ref "U$3") (pin "54") (pinfunction "CH29_54") (pintype "input"))
    )
    (net (code "36") (name "Net-(U$3-CH30)") (class "Default")
      (node (ref "H$30") (pin "P$1") (pinfunction "P$1_P$1") (pintype "bidirectional"))
      (node (ref "U$3") (pin "19") (pinfunction "CH30_19") (pintype "input"))
    )
    (net (code "37") (name "Net-(U$3-CH31)") (class "Default")
      (node (ref "H$31") (pin "P$1") (pinfunction "P$1_P$1") (pintype "bidirectional"))
      (node (ref "U$3") (pin "53") (pinfunction "CH31_53") (pintype "input"))
    )
    (net (code "38") (name "Net-(U$3-CH32)") (class "Default")
      (node (ref "H$32") (pin "P$1") (pinfunction "P$1_P$1") (pintype "bidirectional"))
      (node (ref "U$3") (pin "18") (pinfunction "CH32_18") (pintype "input"))
    )
    (net (code "39") (name "Net-(U$3-CH33)") (class "Default")
      (node (ref "H$33") (pin "P$1") (pinfunction "P$1_P$1") (pintype "bidirectional"))
      (node (ref "U$3") (pin "52") (pinfunction "CH33_52") (pintype "input"))
    )
    (net (code "40") (name "Net-(U$3-CH34)") (class "Default")
      (node (ref "H$34") (pin "P$1") (pinfunction "P$1_P$1") (pintype "bidirectional"))
      (node (ref "U$3") (pin "17") (pinfunction "CH34_17") (pintype "input"))
    )
    (net (code "41") (name "Net-(U$3-CH35)") (class "Default")
      (node (ref "H$35") (pin "P$1") (pinfunction "P$1_P$1") (pintype "bidirectional"))
      (node (ref "U$3") (pin "51") (pinfunction "CH35_51") (pintype "input"))
    )
    (net (code "42") (name "Net-(U$3-CH36)") (class "Default")
      (node (ref "H$36") (pin "P$1") (pinfunction "P$1_P$1") (pintype "bidirectional"))
      (node (ref "U$3") (pin "16") (pinfunction "CH36_16") (pintype "input"))
    )
    (net (code "43") (name "Net-(U$3-CH37)") (class "Default")
      (node (ref "H$37") (pin "P$1") (pinfunction "P$1_P$1") (pintype "bidirectional"))
      (node (ref "U$3") (pin "50") (pinfunction "CH37_50") (pintype "input"))
    )
    (net (code "44") (name "Net-(U$3-CH38)") (class "Default")
      (node (ref "H$38") (pin "P$1") (pinfunction "P$1_P$1") (pintype "bidirectional"))
      (node (ref "U$3") (pin "15") (pinfunction "CH38_15") (pintype "input"))
    )
    (net (code "45") (name "Net-(U$3-CH39)") (class "Default")
      (node (ref "H$39") (pin "P$1") (pinfunction "P$1_P$1") (pintype "bidirectional"))
      (node (ref "U$3") (pin "49") (pinfunction "CH39_49") (pintype "input"))
    )
    (net (code "46") (name "Net-(U$3-CH40)") (class "Default")
      (node (ref "H$40") (pin "P$1") (pinfunction "P$1_P$1") (pintype "bidirectional"))
      (node (ref "U$3") (pin "14") (pinfunction "CH40_14") (pintype "input"))
    )
    (net (code "47") (name "Net-(U$3-CH41)") (class "Default")
      (node (ref "H$41") (pin "P$1") (pinfunction "P$1_P$1") (pintype "bidirectional"))
      (node (ref "U$3") (pin "48") (pinfunction "CH41_48") (pintype "input"))
    )
    (net (code "48") (name "Net-(U$3-CH42)") (class "Default")
      (node (ref "H$42") (pin "P$1") (pinfunction "P$1_P$1") (pintype "bidirectional"))
      (node (ref "U$3") (pin "13") (pinfunction "CH42_13") (pintype "input"))
    )
    (net (code "49") (name "Net-(U$3-CH43)") (class "Default")
      (node (ref "H$43") (pin "P$1") (pinfunction "P$1_P$1") (pintype "bidirectional"))
      (node (ref "U$3") (pin "47") (pinfunction "CH43_47") (pintype "input"))
    )
    (net (code "50") (name "Net-(U$3-CH44)") (class "Default")
      (node (ref "H$44") (pin "P$1") (pinfunction "P$1_P$1") (pintype "bidirectional"))
      (node (ref "U$3") (pin "12") (pinfunction "CH44_12") (pintype "input"))
    )
    (net (code "51") (name "Net-(U$3-CH45)") (class "Default")
      (node (ref "H$45") (pin "P$1") (pinfunction "P$1_P$1") (pintype "bidirectional"))
      (node (ref "U$3") (pin "46") (pinfunction "CH45_46") (pintype "input"))
    )
    (net (code "52") (name "Net-(U$3-CH46)") (class "Default")
      (node (ref "H$46") (pin "P$1") (pinfunction "P$1_P$1") (pintype "bidirectional"))
      (node (ref "U$3") (pin "11") (pinfunction "CH46_11") (pintype "input"))
    )
    (net (code "53") (name "Net-(U$3-CH47)") (class "Default")
      (node (ref "H$47") (pin "P$1") (pinfunction "P$1_P$1") (pintype "bidirectional"))
      (node (ref "U$3") (pin "45") (pinfunction "CH47_45") (pintype "input"))
    )
    (net (code "54") (name "Net-(U$3-CH48)") (class "Default")
      (node (ref "H$48") (pin "P$1") (pinfunction "P$1_P$1") (pintype "bidirectional"))
      (node (ref "U$3") (pin "10") (pinfunction "CH48_10") (pintype "input"))
    )
    (net (code "55") (name "Net-(U$3-CH49)") (class "Default")
      (node (ref "H$49") (pin "P$1") (pinfunction "P$1_P$1") (pintype "bidirectional"))
      (node (ref "U$3") (pin "44") (pinfunction "CH49_44") (pintype "input"))
    )
    (net (code "56") (name "Net-(U$3-CH50)") (class "Default")
      (node (ref "H$50") (pin "P$1") (pinfunction "P$1_P$1") (pintype "bidirectional"))
      (node (ref "U$3") (pin "9") (pinfunction "CH50_9") (pintype "input"))
    )
    (net (code "57") (name "Net-(U$3-CH51)") (class "Default")
      (node (ref "H$51") (pin "P$1") (pinfunction "P$1_P$1") (pintype "bidirectional"))
      (node (ref "U$3") (pin "43") (pinfunction "CH51_43") (pintype "input"))
    )
    (net (code "58") (name "Net-(U$3-CH52)") (class "Default")
      (node (ref "H$52") (pin "P$1") (pinfunction "P$1_P$1") (pintype "bidirectional"))
      (node (ref "U$3") (pin "8") (pinfunction "CH52_8") (pintype "input"))
    )
    (net (code "59") (name "Net-(U$3-CH53)") (class "Default")
      (node (ref "H$53") (pin "P$1") (pinfunction "P$1_P$1") (pintype "bidirectional"))
      (node (ref "U$3") (pin "42") (pinfunction "CH53_42") (pintype "input"))
    )
    (net (code "60") (name "Net-(U$3-CH54)") (class "Default")
      (node (ref "H$54") (pin "P$1") (pinfunction "P$1_P$1") (pintype "bidirectional"))
      (node (ref "U$3") (pin "7") (pinfunction "CH54_7") (pintype "input"))
    )
    (net (code "61") (name "Net-(U$3-CH55)") (class "Default")
      (node (ref "H$55") (pin "P$1") (pinfunction "P$1_P$1") (pintype "bidirectional"))
      (node (ref "U$3") (pin "41") (pinfunction "CH55_41") (pintype "input"))
    )
    (net (code "62") (name "Net-(U$3-CH56)") (class "Default")
      (node (ref "H$56") (pin "P$1") (pinfunction "P$1_P$1") (pintype "bidirectional"))
      (node (ref "U$3") (pin "6") (pinfunction "CH56_6") (pintype "input"))
    )
    (net (code "63") (name "Net-(U$3-CH57)") (class "Default")
      (node (ref "H$57") (pin "P$1") (pinfunction "P$1_P$1") (pintype "bidirectional"))
      (node (ref "U$3") (pin "40") (pinfunction "CH57_40") (pintype "input"))
    )
    (net (code "64") (name "Net-(U$3-CH58)") (class "Default")
      (node (ref "H$58") (pin "P$1") (pinfunction "P$1_P$1") (pintype "bidirectional"))
      (node (ref "U$3") (pin "5") (pinfunction "CH58_5") (pintype "input"))
    )
    (net (code "65") (name "Net-(U$3-CH59)") (class "Default")
      (node (ref "H$59") (pin "P$1") (pinfunction "P$1_P$1") (pintype "bidirectional"))
      (node (ref "U$3") (pin "39") (pinfunction "CH59_39") (pintype "input"))
    )
    (net (code "66") (name "Net-(U$3-CH60)") (class "Default")
      (node (ref "H$60") (pin "P$1") (pinfunction "P$1_P$1") (pintype "bidirectional"))
      (node (ref "U$3") (pin "4") (pinfunction "CH60_4") (pintype "input"))
    )
    (net (code "67") (name "Net-(U$3-CH61)") (class "Default")
      (node (ref "H$61") (pin "P$1") (pinfunction "P$1_P$1") (pintype "bidirectional"))
      (node (ref "U$3") (pin "38") (pinfunction "CH61_38") (pintype "input"))
    )
    (net (code "68") (name "Net-(U$3-CH62)") (class "Default")
      (node (ref "H$62") (pin "P$1") (pinfunction "P$1_P$1") (pintype "bidirectional"))
      (node (ref "U$3") (pin "3") (pinfunction "CH62_3") (pintype "input"))
    )
    (net (code "69") (name "Net-(U$3-CH63)") (class "Default")
      (node (ref "H$63") (pin "P$1") (pinfunction "P$1_P$1") (pintype "bidirectional"))
      (node (ref "U$3") (pin "37") (pinfunction "CH63_37") (pintype "input"))
    )
    (net (code "70") (name "Net-(U$3-CH64)") (class "Default")
      (node (ref "H$64") (pin "P$1") (pinfunction "P$1_P$1") (pintype "bidirectional"))
      (node (ref "U$3") (pin "108") (pinfunction "CH64_108") (pintype "input"))
    )
    (net (code "71") (name "Net-(U$3-CH65)") (class "Default")
      (node (ref "H$65") (pin "P$1") (pinfunction "P$1_P$1") (pintype "bidirectional"))
      (node (ref "U$3") (pin "142") (pinfunction "CH65_142") (pintype "input"))
    )
    (net (code "72") (name "Net-(U$3-CH66)") (class "Default")
      (node (ref "H$66") (pin "P$1") (pinfunction "P$1_P$1") (pintype "bidirectional"))
      (node (ref "U$3") (pin "107") (pinfunction "CH66_107") (pintype "input"))
    )
    (net (code "73") (name "Net-(U$3-CH67)") (class "Default")
      (node (ref "H$67") (pin "P$1") (pinfunction "P$1_P$1") (pintype "bidirectional"))
      (node (ref "U$3") (pin "141") (pinfunction "CH67_141") (pintype "input"))
    )
    (net (code "74") (name "Net-(U$3-CH68)") (class "Default")
      (node (ref "H$68") (pin "P$1") (pinfunction "P$1_P$1") (pintype "bidirectional"))
      (node (ref "U$3") (pin "106") (pinfunction "CH68_106") (pintype "input"))
    )
    (net (code "75") (name "Net-(U$3-CH69)") (class "Default")
      (node (ref "H$69") (pin "P$1") (pinfunction "P$1_P$1") (pintype "bidirectional"))
      (node (ref "U$3") (pin "140") (pinfunction "CH69_140") (pintype "input"))
    )
    (net (code "76") (name "Net-(U$3-CH70)") (class "Default")
      (node (ref "H$70") (pin "P$1") (pinfunction "P$1_P$1") (pintype "bidirectional"))
      (node (ref "U$3") (pin "105") (pinfunction "CH70_105") (pintype "input"))
    )
    (net (code "77") (name "Net-(U$3-CH71)") (class "Default")
      (node (ref "H$71") (pin "P$1") (pinfunction "P$1_P$1") (pintype "bidirectional"))
      (node (ref "U$3") (pin "139") (pinfunction "CH71_139") (pintype "input"))
    )
    (net (code "78") (name "Net-(U$3-CH72)") (class "Default")
      (node (ref "H$72") (pin "P$1") (pinfunction "P$1_P$1") (pintype "bidirectional"))
      (node (ref "U$3") (pin "104") (pinfunction "CH72_104") (pintype "input"))
    )
    (net (code "79") (name "Net-(U$3-CH73)") (class "Default")
      (node (ref "H$73") (pin "P$1") (pinfunction "P$1_P$1") (pintype "bidirectional"))
      (node (ref "U$3") (pin "138") (pinfunction "CH73_138") (pintype "input"))
    )
    (net (code "80") (name "Net-(U$3-CH74)") (class "Default")
      (node (ref "H$74") (pin "P$1") (pinfunction "P$1_P$1") (pintype "bidirectional"))
      (node (ref "U$3") (pin "103") (pinfunction "CH74_103") (pintype "input"))
    )
    (net (code "81") (name "Net-(U$3-CH75)") (class "Default")
      (node (ref "H$75") (pin "P$1") (pinfunction "P$1_P$1") (pintype "bidirectional"))
      (node (ref "U$3") (pin "137") (pinfunction "CH75_137") (pintype "input"))
    )
    (net (code "82") (name "Net-(U$3-CH76)") (class "Default")
      (node (ref "H$76") (pin "P$1") (pinfunction "P$1_P$1") (pintype "bidirectional"))
      (node (ref "U$3") (pin "102") (pinfunction "CH76_102") (pintype "input"))
    )
    (net (code "83") (name "Net-(U$3-CH77)") (class "Default")
      (node (ref "H$77") (pin "P$1") (pinfunction "P$1_P$1") (pintype "bidirectional"))
      (node (ref "U$3") (pin "136") (pinfunction "CH77_136") (pintype "input"))
    )
    (net (code "84") (name "Net-(U$3-CH78)") (class "Default")
      (node (ref "H$78") (pin "P$1") (pinfunction "P$1_P$1") (pintype "bidirectional"))
      (node (ref "U$3") (pin "101") (pinfunction "CH78_101") (pintype "input"))
    )
    (net (code "85") (name "Net-(U$3-CH79)") (class "Default")
      (node (ref "H$79") (pin "P$1") (pinfunction "P$1_P$1") (pintype "bidirectional"))
      (node (ref "U$3") (pin "135") (pinfunction "CH79_135") (pintype "input"))
    )
    (net (code "86") (name "Net-(U$3-CH80)") (class "Default")
      (node (ref "H$80") (pin "P$1") (pinfunction "P$1_P$1") (pintype "bidirectional"))
      (node (ref "U$3") (pin "100") (pinfunction "CH80_100") (pintype "input"))
    )
    (net (code "87") (name "Net-(U$3-CH81)") (class "Default")
      (node (ref "H$81") (pin "P$1") (pinfunction "P$1_P$1") (pintype "bidirectional"))
      (node (ref "U$3") (pin "134") (pinfunction "CH81_134") (pintype "input"))
    )
    (net (code "88") (name "Net-(U$3-CH82)") (class "Default")
      (node (ref "H$82") (pin "P$1") (pinfunction "P$1_P$1") (pintype "bidirectional"))
      (node (ref "U$3") (pin "99") (pinfunction "CH82_99") (pintype "input"))
    )
    (net (code "89") (name "Net-(U$3-CH83)") (class "Default")
      (node (ref "H$83") (pin "P$1") (pinfunction "P$1_P$1") (pintype "bidirectional"))
      (node (ref "U$3") (pin "133") (pinfunction "CH83_133") (pintype "input"))
    )
    (net (code "90") (name "Net-(U$3-CH84)") (class "Default")
      (node (ref "H$84") (pin "P$1") (pinfunction "P$1_P$1") (pintype "bidirectional"))
      (node (ref "U$3") (pin "98") (pinfunction "CH84_98") (pintype "input"))
    )
    (net (code "91") (name "Net-(U$3-CH85)") (class "Default")
      (node (ref "H$85") (pin "P$1") (pinfunction "P$1_P$1") (pintype "bidirectional"))
      (node (ref "U$3") (pin "132") (pinfunction "CH85_132") (pintype "input"))
    )
    (net (code "92") (name "Net-(U$3-CH86)") (class "Default")
      (node (ref "H$86") (pin "P$1") (pinfunction "P$1_P$1") (pintype "bidirectional"))
      (node (ref "U$3") (pin "97") (pinfunction "CH86_97") (pintype "input"))
    )
    (net (code "93") (name "Net-(U$3-CH87)") (class "Default")
      (node (ref "H$87") (pin "P$1") (pinfunction "P$1_P$1") (pintype "bidirectional"))
      (node (ref "U$3") (pin "131") (pinfunction "CH87_131") (pintype "input"))
    )
    (net (code "94") (name "Net-(U$3-CH88)") (class "Default")
      (node (ref "H$88") (pin "P$1") (pinfunction "P$1_P$1") (pintype "bidirectional"))
      (node (ref "U$3") (pin "96") (pinfunction "CH88_96") (pintype "input"))
    )
    (net (code "95") (name "Net-(U$3-CH89)") (class "Default")
      (node (ref "H$89") (pin "P$1") (pinfunction "P$1_P$1") (pintype "bidirectional"))
      (node (ref "U$3") (pin "130") (pinfunction "CH89_130") (pintype "input"))
    )
    (net (code "96") (name "Net-(U$3-CH90)") (class "Default")
      (node (ref "H$90") (pin "P$1") (pinfunction "P$1_P$1") (pintype "bidirectional"))
      (node (ref "U$3") (pin "95") (pinfunction "CH90_95") (pintype "input"))
    )
    (net (code "97") (name "Net-(U$3-CH91)") (class "Default")
      (node (ref "H$91") (pin "P$1") (pinfunction "P$1_P$1") (pintype "bidirectional"))
      (node (ref "U$3") (pin "129") (pinfunction "CH91_129") (pintype "input"))
    )
    (net (code "98") (name "Net-(U$3-CH92)") (class "Default")
      (node (ref "H$92") (pin "P$1") (pinfunction "P$1_P$1") (pintype "bidirectional"))
      (node (ref "U$3") (pin "94") (pinfunction "CH92_94") (pintype "input"))
    )
    (net (code "99") (name "Net-(U$3-CH93)") (class "Default")
      (node (ref "H$93") (pin "P$1") (pinfunction "P$1_P$1") (pintype "bidirectional"))
      (node (ref "U$3") (pin "128") (pinfunction "CH93_128") (pintype "input"))
    )
    (net (code "100") (name "Net-(U$3-CH94)") (class "Default")
      (node (ref "H$94") (pin "P$1") (pinfunction "P$1_P$1") (pintype "bidirectional"))
      (node (ref "U$3") (pin "93") (pinfunction "CH94_93") (pintype "input"))
    )
    (net (code "101") (name "Net-(U$3-CH95)") (class "Default")
      (node (ref "H$95") (pin "P$1") (pinfunction "P$1_P$1") (pintype "bidirectional"))
      (node (ref "U$3") (pin "127") (pinfunction "CH95_127") (pintype "input"))
    )
    (net (code "102") (name "Net-(U$3-CH96)") (class "Default")
      (node (ref "H$96") (pin "P$1") (pinfunction "P$1_P$1") (pintype "bidirectional"))
      (node (ref "U$3") (pin "92") (pinfunction "CH96_92") (pintype "input"))
    )
    (net (code "103") (name "Net-(U$3-CH97)") (class "Default")
      (node (ref "H$97") (pin "P$1") (pinfunction "P$1_P$1") (pintype "bidirectional"))
      (node (ref "U$3") (pin "126") (pinfunction "CH97_126") (pintype "input"))
    )
    (net (code "104") (name "Net-(U$3-CH98)") (class "Default")
      (node (ref "H$98") (pin "P$1") (pinfunction "P$1_P$1") (pintype "bidirectional"))
      (node (ref "U$3") (pin "91") (pinfunction "CH98_91") (pintype "input"))
    )
    (net (code "105") (name "Net-(U$3-CH99)") (class "Default")
      (node (ref "H$99") (pin "P$1") (pinfunction "P$1_P$1") (pintype "bidirectional"))
      (node (ref "U$3") (pin "125") (pinfunction "CH99_125") (pintype "input"))
    )
    (net (code "106") (name "Net-(U$3-CH100)") (class "Default")
      (node (ref "H$100") (pin "P$1") (pinfunction "P$1_P$1") (pintype "bidirectional"))
      (node (ref "U$3") (pin "90") (pinfunction "CH100_90") (pintype "input"))
    )
    (net (code "107") (name "Net-(U$3-CH101)") (class "Default")
      (node (ref "H$101") (pin "P$1") (pinfunction "P$1_P$1") (pintype "bidirectional"))
      (node (ref "U$3") (pin "124") (pinfunction "CH101_124") (pintype "input"))
    )
    (net (code "108") (name "Net-(U$3-CH102)") (class "Default")
      (node (ref "H$102") (pin "P$1") (pinfunction "P$1_P$1") (pintype "bidirectional"))
      (node (ref "U$3") (pin "89") (pinfunction "CH102_89") (pintype "input"))
    )
    (net (code "109") (name "Net-(U$3-CH103)") (class "Default")
      (node (ref "H$103") (pin "P$1") (pinfunction "P$1_P$1") (pintype "bidirectional"))
      (node (ref "U$3") (pin "123") (pinfunction "CH103_123") (pintype "input"))
    )
    (net (code "110") (name "Net-(U$3-CH104)") (class "Default")
      (node (ref "H$104") (pin "P$1") (pinfunction "P$1_P$1") (pintype "bidirectional"))
      (node (ref "U$3") (pin "88") (pinfunction "CH104_88") (pintype "input"))
    )
    (net (code "111") (name "Net-(U$3-CH105)") (class "Default")
      (node (ref "H$105") (pin "P$1") (pinfunction "P$1_P$1") (pintype "bidirectional"))
      (node (ref "U$3") (pin "122") (pinfunction "CH105_122") (pintype "input"))
    )
    (net (code "112") (name "Net-(U$3-CH106)") (class "Default")
      (node (ref "H$106") (pin "P$1") (pinfunction "P$1_P$1") (pintype "bidirectional"))
      (node (ref "U$3") (pin "87") (pinfunction "CH106_87") (pintype "input"))
    )
    (net (code "113") (name "Net-(U$3-CH107)") (class "Default")
      (node (ref "H$107") (pin "P$1") (pinfunction "P$1_P$1") (pintype "bidirectional"))
      (node (ref "U$3") (pin "121") (pinfunction "CH107_121") (pintype "input"))
    )
    (net (code "114") (name "Net-(U$3-CH108)") (class "Default")
      (node (ref "H$108") (pin "P$1") (pinfunction "P$1_P$1") (pintype "bidirectional"))
      (node (ref "U$3") (pin "86") (pinfunction "CH108_86") (pintype "input"))
    )
    (net (code "115") (name "Net-(U$3-CH109)") (class "Default")
      (node (ref "H$109") (pin "P$1") (pinfunction "P$1_P$1") (pintype "bidirectional"))
      (node (ref "U$3") (pin "120") (pinfunction "CH109_120") (pintype "input"))
    )
    (net (code "116") (name "Net-(U$3-CH110)") (class "Default")
      (node (ref "H$110") (pin "P$1") (pinfunction "P$1_P$1") (pintype "bidirectional"))
      (node (ref "U$3") (pin "85") (pinfunction "CH110_85") (pintype "input"))
    )
    (net (code "117") (name "Net-(U$3-CH111)") (class "Default")
      (node (ref "H$111") (pin "P$1") (pinfunction "P$1_P$1") (pintype "bidirectional"))
      (node (ref "U$3") (pin "119") (pinfunction "CH111_119") (pintype "input"))
    )
    (net (code "118") (name "Net-(U$3-CH112)") (class "Default")
      (node (ref "H$112") (pin "P$1") (pinfunction "P$1_P$1") (pintype "bidirectional"))
      (node (ref "U$3") (pin "84") (pinfunction "CH112_84") (pintype "input"))
    )
    (net (code "119") (name "Net-(U$3-CH113)") (class "Default")
      (node (ref "H$113") (pin "P$1") (pinfunction "P$1_P$1") (pintype "bidirectional"))
      (node (ref "U$3") (pin "118") (pinfunction "CH113_118") (pintype "input"))
    )
    (net (code "120") (name "Net-(U$3-CH114)") (class "Default")
      (node (ref "H$114") (pin "P$1") (pinfunction "P$1_P$1") (pintype "bidirectional"))
      (node (ref "U$3") (pin "83") (pinfunction "CH114_83") (pintype "input"))
    )
    (net (code "121") (name "Net-(U$3-CH115)") (class "Default")
      (node (ref "H$115") (pin "P$1") (pinfunction "P$1_P$1") (pintype "bidirectional"))
      (node (ref "U$3") (pin "117") (pinfunction "CH115_117") (pintype "input"))
    )
    (net (code "122") (name "Net-(U$3-CH116)") (class "Default")
      (node (ref "H$116") (pin "P$1") (pinfunction "P$1_P$1") (pintype "bidirectional"))
      (node (ref "U$3") (pin "82") (pinfunction "CH116_82") (pintype "input"))
    )
    (net (code "123") (name "Net-(U$3-CH117)") (class "Default")
      (node (ref "H$117") (pin "P$1") (pinfunction "P$1_P$1") (pintype "bidirectional"))
      (node (ref "U$3") (pin "116") (pinfunction "CH117_116") (pintype "input"))
    )
    (net (code "124") (name "Net-(U$3-CH118)") (class "Default")
      (node (ref "H$118") (pin "P$1") (pinfunction "P$1_P$1") (pintype "bidirectional"))
      (node (ref "U$3") (pin "81") (pinfunction "CH118_81") (pintype "input"))
    )
    (net (code "125") (name "Net-(U$3-CH119)") (class "Default")
      (node (ref "H$119") (pin "P$1") (pinfunction "P$1_P$1") (pintype "bidirectional"))
      (node (ref "U$3") (pin "115") (pinfunction "CH119_115") (pintype "input"))
    )
    (net (code "126") (name "Net-(U$3-CH120)") (class "Default")
      (node (ref "H$120") (pin "P$1") (pinfunction "P$1_P$1") (pintype "bidirectional"))
      (node (ref "U$3") (pin "80") (pinfunction "CH120_80") (pintype "input"))
    )
    (net (code "127") (name "Net-(U$3-CH121)") (class "Default")
      (node (ref "H$121") (pin "P$1") (pinfunction "P$1_P$1") (pintype "bidirectional"))
      (node (ref "U$3") (pin "114") (pinfunction "CH121_114") (pintype "input"))
    )
    (net (code "128") (name "Net-(U$3-CH122)") (class "Default")
      (node (ref "H$122") (pin "P$1") (pinfunction "P$1_P$1") (pintype "bidirectional"))
      (node (ref "U$3") (pin "79") (pinfunction "CH122_79") (pintype "input"))
    )
    (net (code "129") (name "Net-(U$3-CH123)") (class "Default")
      (node (ref "H$123") (pin "P$1") (pinfunction "P$1_P$1") (pintype "bidirectional"))
      (node (ref "U$3") (pin "113") (pinfunction "CH123_113") (pintype "input"))
    )
    (net (code "130") (name "Net-(U$3-CH124)") (class "Default")
      (node (ref "H$124") (pin "P$1") (pinfunction "P$1_P$1") (pintype "bidirectional"))
      (node (ref "U$3") (pin "78") (pinfunction "CH124_78") (pintype "input"))
    )
    (net (code "131") (name "Net-(U$3-CH125)") (class "Default")
      (node (ref "H$125") (pin "P$1") (pinfunction "P$1_P$1") (pintype "bidirectional"))
      (node (ref "U$3") (pin "112") (pinfunction "CH125_112") (pintype "input"))
    )
    (net (code "132") (name "Net-(U$3-CH126)") (class "Default")
      (node (ref "H$126") (pin "P$1") (pinfunction "P$1_P$1") (pintype "bidirectional"))
      (node (ref "U$3") (pin "77") (pinfunction "CH126_77") (pintype "input"))
    )
    (net (code "133") (name "Net-(U$3-CH127)") (class "Default")
      (node (ref "H$127") (pin "P$1") (pinfunction "P$1_P$1") (pintype "bidirectional"))
      (node (ref "U$3") (pin "111") (pinfunction "CH127_111") (pintype "input"))
    )
    (net (code "134") (name "Net-(U$3-GND3)") (class "Default")
      (node (ref "U$3") (pin "110") (pinfunction "GND7_110") (pintype "power_in"))
      (node (ref "U$3") (pin "144") (pinfunction "GND8_144") (pintype "power_in"))
      (node (ref "U$3") (pin "36") (pinfunction "GND3_36") (pintype "power_in"))
      (node (ref "U$3") (pin "70") (pinfunction "GND4_70") (pintype "power_in"))
    )
    (net (code "135") (name "unconnected-(U$1-CH0-PadP$0)") (class "Default")
      (node (ref "U$1") (pin "P$0") (pinfunction "CH0_P$0") (pintype "bidirectional"))
    )
    (net (code "136") (name "unconnected-(U$1-CH1-PadP$1)") (class "Default")
      (node (ref "U$1") (pin "P$1") (pinfunction "CH1_P$1") (pintype "bidirectional"))
    )
    (net (code "137") (name "unconnected-(U$1-CH2-PadP$2)") (class "Default")
      (node (ref "U$1") (pin "P$2") (pinfunction "CH2_P$2") (pintype "bidirectional"))
    )
    (net (code "138") (name "unconnected-(U$1-CH3-PadP$3)") (class "Default")
      (node (ref "U$1") (pin "P$3") (pinfunction "CH3_P$3") (pintype "bidirectional"))
    )
    (net (code "139") (name "unconnected-(U$1-CH4-PadP$4)") (class "Default")
      (node (ref "U$1") (pin "P$4") (pinfunction "CH4_P$4") (pintype "bidirectional"))
    )
    (net (code "140") (name "unconnected-(U$1-CH5-PadP$5)") (class "Default")
      (node (ref "U$1") (pin "P$5") (pinfunction "CH5_P$5") (pintype "bidirectional"))
    )
    (net (code "141") (name "unconnected-(U$1-CH6-PadP$6)") (class "Default")
      (node (ref "U$1") (pin "P$6") (pinfunction "CH6_P$6") (pintype "bidirectional"))
    )
    (net (code "142") (name "unconnected-(U$1-CH7-PadP$7)") (class "Default")
      (node (ref "U$1") (pin "P$7") (pinfunction "CH7_P$7") (pintype "bidirectional"))
    )
    (net (code "143") (name "unconnected-(U$1-CH8-PadP$8)") (class "Default")
      (node (ref "U$1") (pin "P$8") (pinfunction "CH8_P$8") (pintype "bidirectional"))
    )
    (net (code "144") (name "unconnected-(U$1-CH9-PadP$9)") (class "Default")
      (node (ref "U$1") (pin "P$9") (pinfunction "CH9_P$9") (pintype "bidirectional"))
    )
    (net (code "145") (name "unconnected-(U$1-CH10-PadP$10)") (class "Default")
      (node (ref "U$1") (pin "P$10") (pinfunction "CH10_P$10") (pintype "bidirectional"))
    )
    (net (code "146") (name "unconnected-(U$1-CH11-PadP$11)") (class "Default")
      (node (ref "U$1") (pin "P$11") (pinfunction "CH11_P$11") (pintype "bidirectional"))
    )
    (net (code "147") (name "unconnected-(U$1-CH12-PadP$12)") (class "Default")
      (node (ref "U$1") (pin "P$12") (pinfunction "CH12_P$12") (pintype "bidirectional"))
    )
    (net (code "148") (name "unconnected-(U$1-CH13-PadP$13)") (class "Default")
      (node (ref "U$1") (pin "P$13") (pinfunction "CH13_P$13") (pintype "bidirectional"))
    )
    (net (code "149") (name "unconnected-(U$1-CH14-PadP$14)") (class "Default")
      (node (ref "U$1") (pin "P$14") (pinfunction "CH14_P$14") (pintype "bidirectional"))
    )
    (net (code "150") (name "unconnected-(U$1-CH15-PadP$15)") (class "Default")
      (node (ref "U$1") (pin "P$15") (pinfunction "CH15_P$15") (pintype "bidirectional"))
    )
    (net (code "151") (name "unconnected-(U$1-CH16-PadP$16)") (class "Default")
      (node (ref "U$1") (pin "P$16") (pinfunction "CH16_P$16") (pintype "bidirectional"))
    )
    (net (code "152") (name "unconnected-(U$1-CH17-PadP$17)") (class "Default")
      (node (ref "U$1") (pin "P$17") (pinfunction "CH17_P$17") (pintype "bidirectional"))
    )
    (net (code "153") (name "unconnected-(U$1-CH18-PadP$18)") (class "Default")
      (node (ref "U$1") (pin "P$18") (pinfunction "CH18_P$18") (pintype "bidirectional"))
    )
    (net (code "154") (name "unconnected-(U$1-CH19-PadP$19)") (class "Default")
      (node (ref "U$1") (pin "P$19") (pinfunction "CH19_P$19") (pintype "bidirectional"))
    )
    (net (code "155") (name "unconnected-(U$1-CH20-PadP$20)") (class "Default")
      (node (ref "U$1") (pin "P$20") (pinfunction "CH20_P$20") (pintype "bidirectional"))
    )
    (net (code "156") (name "unconnected-(U$1-CH21-PadP$21)") (class "Default")
      (node (ref "U$1") (pin "P$21") (pinfunction "CH21_P$21") (pintype "bidirectional"))
    )
    (net (code "157") (name "unconnected-(U$1-CH22-PadP$22)") (class "Default")
      (node (ref "U$1") (pin "P$22") (pinfunction "CH22_P$22") (pintype "bidirectional"))
    )
    (net (code "158") (name "unconnected-(U$1-CH23-PadP$23)") (class "Default")
      (node (ref "U$1") (pin "P$23") (pinfunction "CH23_P$23") (pintype "bidirectional"))
    )
    (net (code "159") (name "unconnected-(U$1-CH24-PadP$24)") (class "Default")
      (node (ref "U$1") (pin "P$24") (pinfunction "CH24_P$24") (pintype "bidirectional"))
    )
    (net (code "160") (name "unconnected-(U$1-CH25-PadP$25)") (class "Default")
      (node (ref "U$1") (pin "P$25") (pinfunction "CH25_P$25") (pintype "bidirectional"))
    )
    (net (code "161") (name "unconnected-(U$1-CH26-PadP$26)") (class "Default")
      (node (ref "U$1") (pin "P$26") (pinfunction "CH26_P$26") (pintype "bidirectional"))
    )
    (net (code "162") (name "unconnected-(U$1-CH27-PadP$27)") (class "Default")
      (node (ref "U$1") (pin "P$27") (pinfunction "CH27_P$27") (pintype "bidirectional"))
    )
    (net (code "163") (name "unconnected-(U$1-CH28-PadP$28)") (class "Default")
      (node (ref "U$1") (pin "P$28") (pinfunction "CH28_P$28") (pintype "bidirectional"))
    )
    (net (code "164") (name "unconnected-(U$1-CH29-PadP$29)") (class "Default")
      (node (ref "U$1") (pin "P$29") (pinfunction "CH29_P$29") (pintype "bidirectional"))
    )
    (net (code "165") (name "unconnected-(U$1-CH30-PadP$30)") (class "Default")
      (node (ref "U$1") (pin "P$30") (pinfunction "CH30_P$30") (pintype "bidirectional"))
    )
    (net (code "166") (name "unconnected-(U$1-CH31-PadP$31)") (class "Default")
      (node (ref "U$1") (pin "P$31") (pinfunction "CH31_P$31") (pintype "bidirectional"))
    )
    (net (code "167") (name "unconnected-(U$1-CH32-PadP$32)") (class "Default")
      (node (ref "U$1") (pin "P$32") (pinfunction "CH32_P$32") (pintype "bidirectional"))
    )
    (net (code "168") (name "unconnected-(U$1-CH33-PadP$33)") (class "Default")
      (node (ref "U$1") (pin "P$33") (pinfunction "CH33_P$33") (pintype "bidirectional"))
    )
    (net (code "169") (name "unconnected-(U$1-CH34-PadP$34)") (class "Default")
      (node (ref "U$1") (pin "P$34") (pinfunction "CH34_P$34") (pintype "bidirectional"))
    )
    (net (code "170") (name "unconnected-(U$1-CH35-PadP$35)") (class "Default")
      (node (ref "U$1") (pin "P$35") (pinfunction "CH35_P$35") (pintype "bidirectional"))
    )
    (net (code "171") (name "unconnected-(U$1-CH36-PadP$36)") (class "Default")
      (node (ref "U$1") (pin "P$36") (pinfunction "CH36_P$36") (pintype "bidirectional"))
    )
    (net (code "172") (name "unconnected-(U$1-CH37-PadP$37)") (class "Default")
      (node (ref "U$1") (pin "P$37") (pinfunction "CH37_P$37") (pintype "bidirectional"))
    )
    (net (code "173") (name "unconnected-(U$1-CH38-PadP$38)") (class "Default")
      (node (ref "U$1") (pin "P$38") (pinfunction "CH38_P$38") (pintype "bidirectional"))
    )
    (net (code "174") (name "unconnected-(U$1-CH39-PadP$39)") (class "Default")
      (node (ref "U$1") (pin "P$39") (pinfunction "CH39_P$39") (pintype "bidirectional"))
    )
    (net (code "175") (name "unconnected-(U$1-CH40-PadP$40)") (class "Default")
      (node (ref "U$1") (pin "P$40") (pinfunction "CH40_P$40") (pintype "bidirectional"))
    )
    (net (code "176") (name "unconnected-(U$1-CH41-PadP$41)") (class "Default")
      (node (ref "U$1") (pin "P$41") (pinfunction "CH41_P$41") (pintype "bidirectional"))
    )
    (net (code "177") (name "unconnected-(U$1-CH42-PadP$42)") (class "Default")
      (node (ref "U$1") (pin "P$42") (pinfunction "CH42_P$42") (pintype "bidirectional"))
    )
    (net (code "178") (name "unconnected-(U$1-CH43-PadP$43)") (class "Default")
      (node (ref "U$1") (pin "P$43") (pinfunction "CH43_P$43") (pintype "bidirectional"))
    )
    (net (code "179") (name "unconnected-(U$1-CH44-PadP$44)") (class "Default")
      (node (ref "U$1") (pin "P$44") (pinfunction "CH44_P$44") (pintype "bidirectional"))
    )
    (net (code "180") (name "unconnected-(U$1-CH45-PadP$45)") (class "Default")
      (node (ref "U$1") (pin "P$45") (pinfunction "CH45_P$45") (pintype "bidirectional"))
    )
    (net (code "181") (name "unconnected-(U$1-CH46-PadP$46)") (class "Default")
      (node (ref "U$1") (pin "P$46") (pinfunction "CH46_P$46") (pintype "bidirectional"))
    )
    (net (code "182") (name "unconnected-(U$1-CH47-PadP$47)") (class "Default")
      (node (ref "U$1") (pin "P$47") (pinfunction "CH47_P$47") (pintype "bidirectional"))
    )
    (net (code "183") (name "unconnected-(U$1-CH48-PadP$48)") (class "Default")
      (node (ref "U$1") (pin "P$48") (pinfunction "CH48_P$48") (pintype "bidirectional"))
    )
    (net (code "184") (name "unconnected-(U$1-CH49-PadP$49)") (class "Default")
      (node (ref "U$1") (pin "P$49") (pinfunction "CH49_P$49") (pintype "bidirectional"))
    )
    (net (code "185") (name "unconnected-(U$1-CH50-PadP$50)") (class "Default")
      (node (ref "U$1") (pin "P$50") (pinfunction "CH50_P$50") (pintype "bidirectional"))
    )
    (net (code "186") (name "unconnected-(U$1-CH51-PadP$51)") (class "Default")
      (node (ref "U$1") (pin "P$51") (pinfunction "CH51_P$51") (pintype "bidirectional"))
    )
    (net (code "187") (name "unconnected-(U$1-CH52-PadP$52)") (class "Default")
      (node (ref "U$1") (pin "P$52") (pinfunction "CH52_P$52") (pintype "bidirectional"))
    )
    (net (code "188") (name "unconnected-(U$1-CH53-PadP$53)") (class "Default")
      (node (ref "U$1") (pin "P$53") (pinfunction "CH53_P$53") (pintype "bidirectional"))
    )
    (net (code "189") (name "unconnected-(U$1-CH54-PadP$54)") (class "Default")
      (node (ref "U$1") (pin "P$54") (pinfunction "CH54_P$54") (pintype "bidirectional"))
    )
    (net (code "190") (name "unconnected-(U$1-CH55-PadP$55)") (class "Default")
      (node (ref "U$1") (pin "P$55") (pinfunction "CH55_P$55") (pintype "bidirectional"))
    )
    (net (code "191") (name "unconnected-(U$1-CH56-PadP$56)") (class "Default")
      (node (ref "U$1") (pin "P$56") (pinfunction "CH56_P$56") (pintype "bidirectional"))
    )
    (net (code "192") (name "unconnected-(U$1-CH57-PadP$57)") (class "Default")
      (node (ref "U$1") (pin "P$57") (pinfunction "CH57_P$57") (pintype "bidirectional"))
    )
    (net (code "193") (name "unconnected-(U$1-CH58-PadP$58)") (class "Default")
      (node (ref "U$1") (pin "P$58") (pinfunction "CH58_P$58") (pintype "bidirectional"))
    )
    (net (code "194") (name "unconnected-(U$1-CH59-PadP$59)") (class "Default")
      (node (ref "U$1") (pin "P$59") (pinfunction "CH59_P$59") (pintype "bidirectional"))
    )
    (net (code "195") (name "unconnected-(U$1-CH60-PadP$60)") (class "Default")
      (node (ref "U$1") (pin "P$60") (pinfunction "CH60_P$60") (pintype "bidirectional"))
    )
    (net (code "196") (name "unconnected-(U$1-CH61-PadP$61)") (class "Default")
      (node (ref "U$1") (pin "P$61") (pinfunction "CH61_P$61") (pintype "bidirectional"))
    )
    (net (code "197") (name "unconnected-(U$1-CH62-PadP$62)") (class "Default")
      (node (ref "U$1") (pin "P$62") (pinfunction "CH62_P$62") (pintype "bidirectional"))
    )
    (net (code "198") (name "unconnected-(U$1-CH63-PadP$63)") (class "Default")
      (node (ref "U$1") (pin "P$63") (pinfunction "CH63_P$63") (pintype "bidirectional"))
    )
    (net (code "199") (name "unconnected-(U$1-PadGND3)") (class "Default")
      (node (ref "U$1") (pin "GND3") (pinfunction "GND3_GND3") (pintype "bidirectional"))
    )
    (net (code "200") (name "unconnected-(U$1-PadGND4)") (class "Default")
      (node (ref "U$1") (pin "GND4") (pinfunction "GND4_GND4") (pintype "bidirectional"))
    )
    (net (code "201") (name "unconnected-(U$1-PadREF1)") (class "Default")
      (node (ref "U$1") (pin "REF1") (pinfunction "REF1_REF1") (pintype "bidirectional"))
    )
    (net (code "202") (name "unconnected-(U$1-PadREF2)") (class "Default")
      (node (ref "U$1") (pin "REF2") (pinfunction "REF2_REF2") (pintype "bidirectional"))
    )
    (net (code "203") (name "unconnected-(U$2-CH0-PadP$0)") (class "Default")
      (node (ref "U$2") (pin "P$0") (pinfunction "CH0_P$0") (pintype "bidirectional"))
    )
    (net (code "204") (name "unconnected-(U$2-CH1-PadP$1)") (class "Default")
      (node (ref "U$2") (pin "P$1") (pinfunction "CH1_P$1") (pintype "bidirectional"))
    )
    (net (code "205") (name "unconnected-(U$2-CH2-PadP$2)") (class "Default")
      (node (ref "U$2") (pin "P$2") (pinfunction "CH2_P$2") (pintype "bidirectional"))
    )
    (net (code "206") (name "unconnected-(U$2-CH3-PadP$3)") (class "Default")
      (node (ref "U$2") (pin "P$3") (pinfunction "CH3_P$3") (pintype "bidirectional"))
    )
    (net (code "207") (name "unconnected-(U$2-CH4-PadP$4)") (class "Default")
      (node (ref "U$2") (pin "P$4") (pinfunction "CH4_P$4") (pintype "bidirectional"))
    )
    (net (code "208") (name "unconnected-(U$2-CH5-PadP$5)") (class "Default")
      (node (ref "U$2") (pin "P$5") (pinfunction "CH5_P$5") (pintype "bidirectional"))
    )
    (net (code "209") (name "unconnected-(U$2-CH6-PadP$6)") (class "Default")
      (node (ref "U$2") (pin "P$6") (pinfunction "CH6_P$6") (pintype "bidirectional"))
    )
    (net (code "210") (name "unconnected-(U$2-CH7-PadP$7)") (class "Default")
      (node (ref "U$2") (pin "P$7") (pinfunction "CH7_P$7") (pintype "bidirectional"))
    )
    (net (code "211") (name "unconnected-(U$2-CH8-PadP$8)") (class "Default")
      (node (ref "U$2") (pin "P$8") (pinfunction "CH8_P$8") (pintype "bidirectional"))
    )
    (net (code "212") (name "unconnected-(U$2-CH9-PadP$9)") (class "Default")
      (node (ref "U$2") (pin "P$9") (pinfunction "CH9_P$9") (pintype "bidirectional"))
    )
    (net (code "213") (name "unconnected-(U$2-CH10-PadP$10)") (class "Default")
      (node (ref "U$2") (pin "P$10") (pinfunction "CH10_P$10") (pintype "bidirectional"))
    )
    (net (code "214") (name "unconnected-(U$2-CH11-PadP$11)") (class "Default")
      (node (ref "U$2") (pin "P$11") (pinfunction "CH11_P$11") (pintype "bidirectional"))
    )
    (net (code "215") (name "unconnected-(U$2-CH12-PadP$12)") (class "Default")
      (node (ref "U$2") (pin "P$12") (pinfunction "CH12_P$12") (pintype "bidirectional"))
    )
    (net (code "216") (name "unconnected-(U$2-CH13-PadP$13)") (class "Default")
      (node (ref "U$2") (pin "P$13") (pinfunction "CH13_P$13") (pintype "bidirectional"))
    )
    (net (code "217") (name "unconnected-(U$2-CH14-PadP$14)") (class "Default")
      (node (ref "U$2") (pin "P$14") (pinfunction "CH14_P$14") (pintype "bidirectional"))
    )
    (net (code "218") (name "unconnected-(U$2-CH15-PadP$15)") (class "Default")
      (node (ref "U$2") (pin "P$15") (pinfunction "CH15_P$15") (pintype "bidirectional"))
    )
    (net (code "219") (name "unconnected-(U$2-CH16-PadP$16)") (class "Default")
      (node (ref "U$2") (pin "P$16") (pinfunction "CH16_P$16") (pintype "bidirectional"))
    )
    (net (code "220") (name "unconnected-(U$2-CH17-PadP$17)") (class "Default")
      (node (ref "U$2") (pin "P$17") (pinfunction "CH17_P$17") (pintype "bidirectional"))
    )
    (net (code "221") (name "unconnected-(U$2-CH18-PadP$18)") (class "Default")
      (node (ref "U$2") (pin "P$18") (pinfunction "CH18_P$18") (pintype "bidirectional"))
    )
    (net (code "222") (name "unconnected-(U$2-CH19-PadP$19)") (class "Default")
      (node (ref "U$2") (pin "P$19") (pinfunction "CH19_P$19") (pintype "bidirectional"))
    )
    (net (code "223") (name "unconnected-(U$2-CH20-PadP$20)") (class "Default")
      (node (ref "U$2") (pin "P$20") (pinfunction "CH20_P$20") (pintype "bidirectional"))
    )
    (net (code "224") (name "unconnected-(U$2-CH21-PadP$21)") (class "Default")
      (node (ref "U$2") (pin "P$21") (pinfunction "CH21_P$21") (pintype "bidirectional"))
    )
    (net (code "225") (name "unconnected-(U$2-CH22-PadP$22)") (class "Default")
      (node (ref "U$2") (pin "P$22") (pinfunction "CH22_P$22") (pintype "bidirectional"))
    )
    (net (code "226") (name "unconnected-(U$2-CH23-PadP$23)") (class "Default")
      (node (ref "U$2") (pin "P$23") (pinfunction "CH23_P$23") (pintype "bidirectional"))
    )
    (net (code "227") (name "unconnected-(U$2-CH24-PadP$24)") (class "Default")
      (node (ref "U$2") (pin "P$24") (pinfunction "CH24_P$24") (pintype "bidirectional"))
    )
    (net (code "228") (name "unconnected-(U$2-CH25-PadP$25)") (class "Default")
      (node (ref "U$2") (pin "P$25") (pinfunction "CH25_P$25") (pintype "bidirectional"))
    )
    (net (code "229") (name "unconnected-(U$2-CH26-PadP$26)") (class "Default")
      (node (ref "U$2") (pin "P$26") (pinfunction "CH26_P$26") (pintype "bidirectional"))
    )
    (net (code "230") (name "unconnected-(U$2-CH27-PadP$27)") (class "Default")
      (node (ref "U$2") (pin "P$27") (pinfunction "CH27_P$27") (pintype "bidirectional"))
    )
    (net (code "231") (name "unconnected-(U$2-CH28-PadP$28)") (class "Default")
      (node (ref "U$2") (pin "P$28") (pinfunction "CH28_P$28") (pintype "bidirectional"))
    )
    (net (code "232") (name "unconnected-(U$2-CH29-PadP$29)") (class "Default")
      (node (ref "U$2") (pin "P$29") (pinfunction "CH29_P$29") (pintype "bidirectional"))
    )
    (net (code "233") (name "unconnected-(U$2-CH30-PadP$30)") (class "Default")
      (node (ref "U$2") (pin "P$30") (pinfunction "CH30_P$30") (pintype "bidirectional"))
    )
    (net (code "234") (name "unconnected-(U$2-CH31-PadP$31)") (class "Default")
      (node (ref "U$2") (pin "P$31") (pinfunction "CH31_P$31") (pintype "bidirectional"))
    )
    (net (code "235") (name "unconnected-(U$2-CH32-PadP$32)") (class "Default")
      (node (ref "U$2") (pin "P$32") (pinfunction "CH32_P$32") (pintype "bidirectional"))
    )
    (net (code "236") (name "unconnected-(U$2-CH33-PadP$33)") (class "Default")
      (node (ref "U$2") (pin "P$33") (pinfunction "CH33_P$33") (pintype "bidirectional"))
    )
    (net (code "237") (name "unconnected-(U$2-CH34-PadP$34)") (class "Default")
      (node (ref "U$2") (pin "P$34") (pinfunction "CH34_P$34") (pintype "bidirectional"))
    )
    (net (code "238") (name "unconnected-(U$2-CH35-PadP$35)") (class "Default")
      (node (ref "U$2") (pin "P$35") (pinfunction "CH35_P$35") (pintype "bidirectional"))
    )
    (net (code "239") (name "unconnected-(U$2-CH36-PadP$36)") (class "Default")
      (node (ref "U$2") (pin "P$36") (pinfunction "CH36_P$36") (pintype "bidirectional"))
    )
    (net (code "240") (name "unconnected-(U$2-CH37-PadP$37)") (class "Default")
      (node (ref "U$2") (pin "P$37") (pinfunction "CH37_P$37") (pintype "bidirectional"))
    )
    (net (code "241") (name "unconnected-(U$2-CH38-PadP$38)") (class "Default")
      (node (ref "U$2") (pin "P$38") (pinfunction "CH38_P$38") (pintype "bidirectional"))
    )
    (net (code "242") (name "unconnected-(U$2-CH39-PadP$39)") (class "Default")
      (node (ref "U$2") (pin "P$39") (pinfunction "CH39_P$39") (pintype "bidirectional"))
    )
    (net (code "243") (name "unconnected-(U$2-CH40-PadP$40)") (class "Default")
      (node (ref "U$2") (pin "P$40") (pinfunction "CH40_P$40") (pintype "bidirectional"))
    )
    (net (code "244") (name "unconnected-(U$2-CH41-PadP$41)") (class "Default")
      (node (ref "U$2") (pin "P$41") (pinfunction "CH41_P$41") (pintype "bidirectional"))
    )
    (net (code "245") (name "unconnected-(U$2-CH42-PadP$42)") (class "Default")
      (node (ref "U$2") (pin "P$42") (pinfunction "CH42_P$42") (pintype "bidirectional"))
    )
    (net (code "246") (name "unconnected-(U$2-CH43-PadP$43)") (class "Default")
      (node (ref "U$2") (pin "P$43") (pinfunction "CH43_P$43") (pintype "bidirectional"))
    )
    (net (code "247") (name "unconnected-(U$2-CH44-PadP$44)") (class "Default")
      (node (ref "U$2") (pin "P$44") (pinfunction "CH44_P$44") (pintype "bidirectional"))
    )
    (net (code "248") (name "unconnected-(U$2-CH45-PadP$45)") (class "Default")
      (node (ref "U$2") (pin "P$45") (pinfunction "CH45_P$45") (pintype "bidirectional"))
    )
    (net (code "249") (name "unconnected-(U$2-CH46-PadP$46)") (class "Default")
      (node (ref "U$2") (pin "P$46") (pinfunction "CH46_P$46") (pintype "bidirectional"))
    )
    (net (code "250") (name "unconnected-(U$2-CH47-PadP$47)") (class "Default")
      (node (ref "U$2") (pin "P$47") (pinfunction "CH47_P$47") (pintype "bidirectional"))
    )
    (net (code "251") (name "unconnected-(U$2-CH48-PadP$48)") (class "Default")
      (node (ref "U$2") (pin "P$48") (pinfunction "CH48_P$48") (pintype "bidirectional"))
    )
    (net (code "252") (name "unconnected-(U$2-CH49-PadP$49)") (class "Default")
      (node (ref "U$2") (pin "P$49") (pinfunction "CH49_P$49") (pintype "bidirectional"))
    )
    (net (code "253") (name "unconnected-(U$2-CH50-PadP$50)") (class "Default")
      (node (ref "U$2") (pin "P$50") (pinfunction "CH50_P$50") (pintype "bidirectional"))
    )
    (net (code "254") (name "unconnected-(U$2-CH51-PadP$51)") (class "Default")
      (node (ref "U$2") (pin "P$51") (pinfunction "CH51_P$51") (pintype "bidirectional"))
    )
    (net (code "255") (name "unconnected-(U$2-CH52-PadP$52)") (class "Default")
      (node (ref "U$2") (pin "P$52") (pinfunction "CH52_P$52") (pintype "bidirectional"))
    )
    (net (code "256") (name "unconnected-(U$2-CH53-PadP$53)") (class "Default")
      (node (ref "U$2") (pin "P$53") (pinfunction "CH53_P$53") (pintype "bidirectional"))
    )
    (net (code "257") (name "unconnected-(U$2-CH54-PadP$54)") (class "Default")
      (node (ref "U$2") (pin "P$54") (pinfunction "CH54_P$54") (pintype "bidirectional"))
    )
    (net (code "258") (name "unconnected-(U$2-CH55-PadP$55)") (class "Default")
      (node (ref "U$2") (pin "P$55") (pinfunction "CH55_P$55") (pintype "bidirectional"))
    )
    (net (code "259") (name "unconnected-(U$2-CH56-PadP$56)") (class "Default")
      (node (ref "U$2") (pin "P$56") (pinfunction "CH56_P$56") (pintype "bidirectional"))
    )
    (net (code "260") (name "unconnected-(U$2-CH57-PadP$57)") (class "Default")
      (node (ref "U$2") (pin "P$57") (pinfunction "CH57_P$57") (pintype "bidirectional"))
    )
    (net (code "261") (name "unconnected-(U$2-CH58-PadP$58)") (class "Default")
      (node (ref "U$2") (pin "P$58") (pinfunction "CH58_P$58") (pintype "bidirectional"))
    )
    (net (code "262") (name "unconnected-(U$2-CH59-PadP$59)") (class "Default")
      (node (ref "U$2") (pin "P$59") (pinfunction "CH59_P$59") (pintype "bidirectional"))
    )
    (net (code "263") (name "unconnected-(U$2-CH60-PadP$60)") (class "Default")
      (node (ref "U$2") (pin "P$60") (pinfunction "CH60_P$60") (pintype "bidirectional"))
    )
    (net (code "264") (name "unconnected-(U$2-CH61-PadP$61)") (class "Default")
      (node (ref "U$2") (pin "P$61") (pinfunction "CH61_P$61") (pintype "bidirectional"))
    )
    (net (code "265") (name "unconnected-(U$2-CH62-PadP$62)") (class "Default")
      (node (ref "U$2") (pin "P$62") (pinfunction "CH62_P$62") (pintype "bidirectional"))
    )
    (net (code "266") (name "unconnected-(U$2-CH63-PadP$63)") (class "Default")
      (node (ref "U$2") (pin "P$63") (pinfunction "CH63_P$63") (pintype "bidirectional"))
    )
    (net (code "267") (name "unconnected-(U$2-PadGND1)") (class "Default")
      (node (ref "U$2") (pin "GND1") (pinfunction "GND1_GND1") (pintype "bidirectional"))
    )
    (net (code "268") (name "unconnected-(U$2-PadGND2)") (class "Default")
      (node (ref "U$2") (pin "GND2") (pinfunction "GND2_GND2") (pintype "bidirectional"))
    )
    (net (code "269") (name "unconnected-(U$2-PadREF1)") (class "Default")
      (node (ref "U$2") (pin "REF1") (pinfunction "REF1_REF1") (pintype "bidirectional"))
    )
    (net (code "270") (name "unconnected-(U$2-PadREF2)") (class "Default")
      (node (ref "U$2") (pin "REF2") (pinfunction "REF2_REF2") (pintype "bidirectional"))
    )
    (net (code "271") (name "unconnected-(U$3-REF1-Pad2)") (class "Default")
      (node (ref "U$3") (pin "2") (pinfunction "REF1_2") (pintype "input"))
    )
    (net (code "272") (name "unconnected-(U$3-REF2-Pad69)") (class "Default")
      (node (ref "U$3") (pin "69") (pinfunction "REF2_69") (pintype "input"))
    )
    (net (code "273") (name "unconnected-(U$3-REF3-Pad76)") (class "Default")
      (node (ref "U$3") (pin "76") (pinfunction "REF3_76") (pintype "input"))
    )
    (net (code "274") (name "unconnected-(U$3-REF4-Pad143)") (class "Default")
      (node (ref "U$3") (pin "143") (pinfunction "REF4_143") (pintype "input"))
    )
  )
)
